# Vocodec_rev2_2.net
KiCad netlist of a schematic drawn in EAGLE
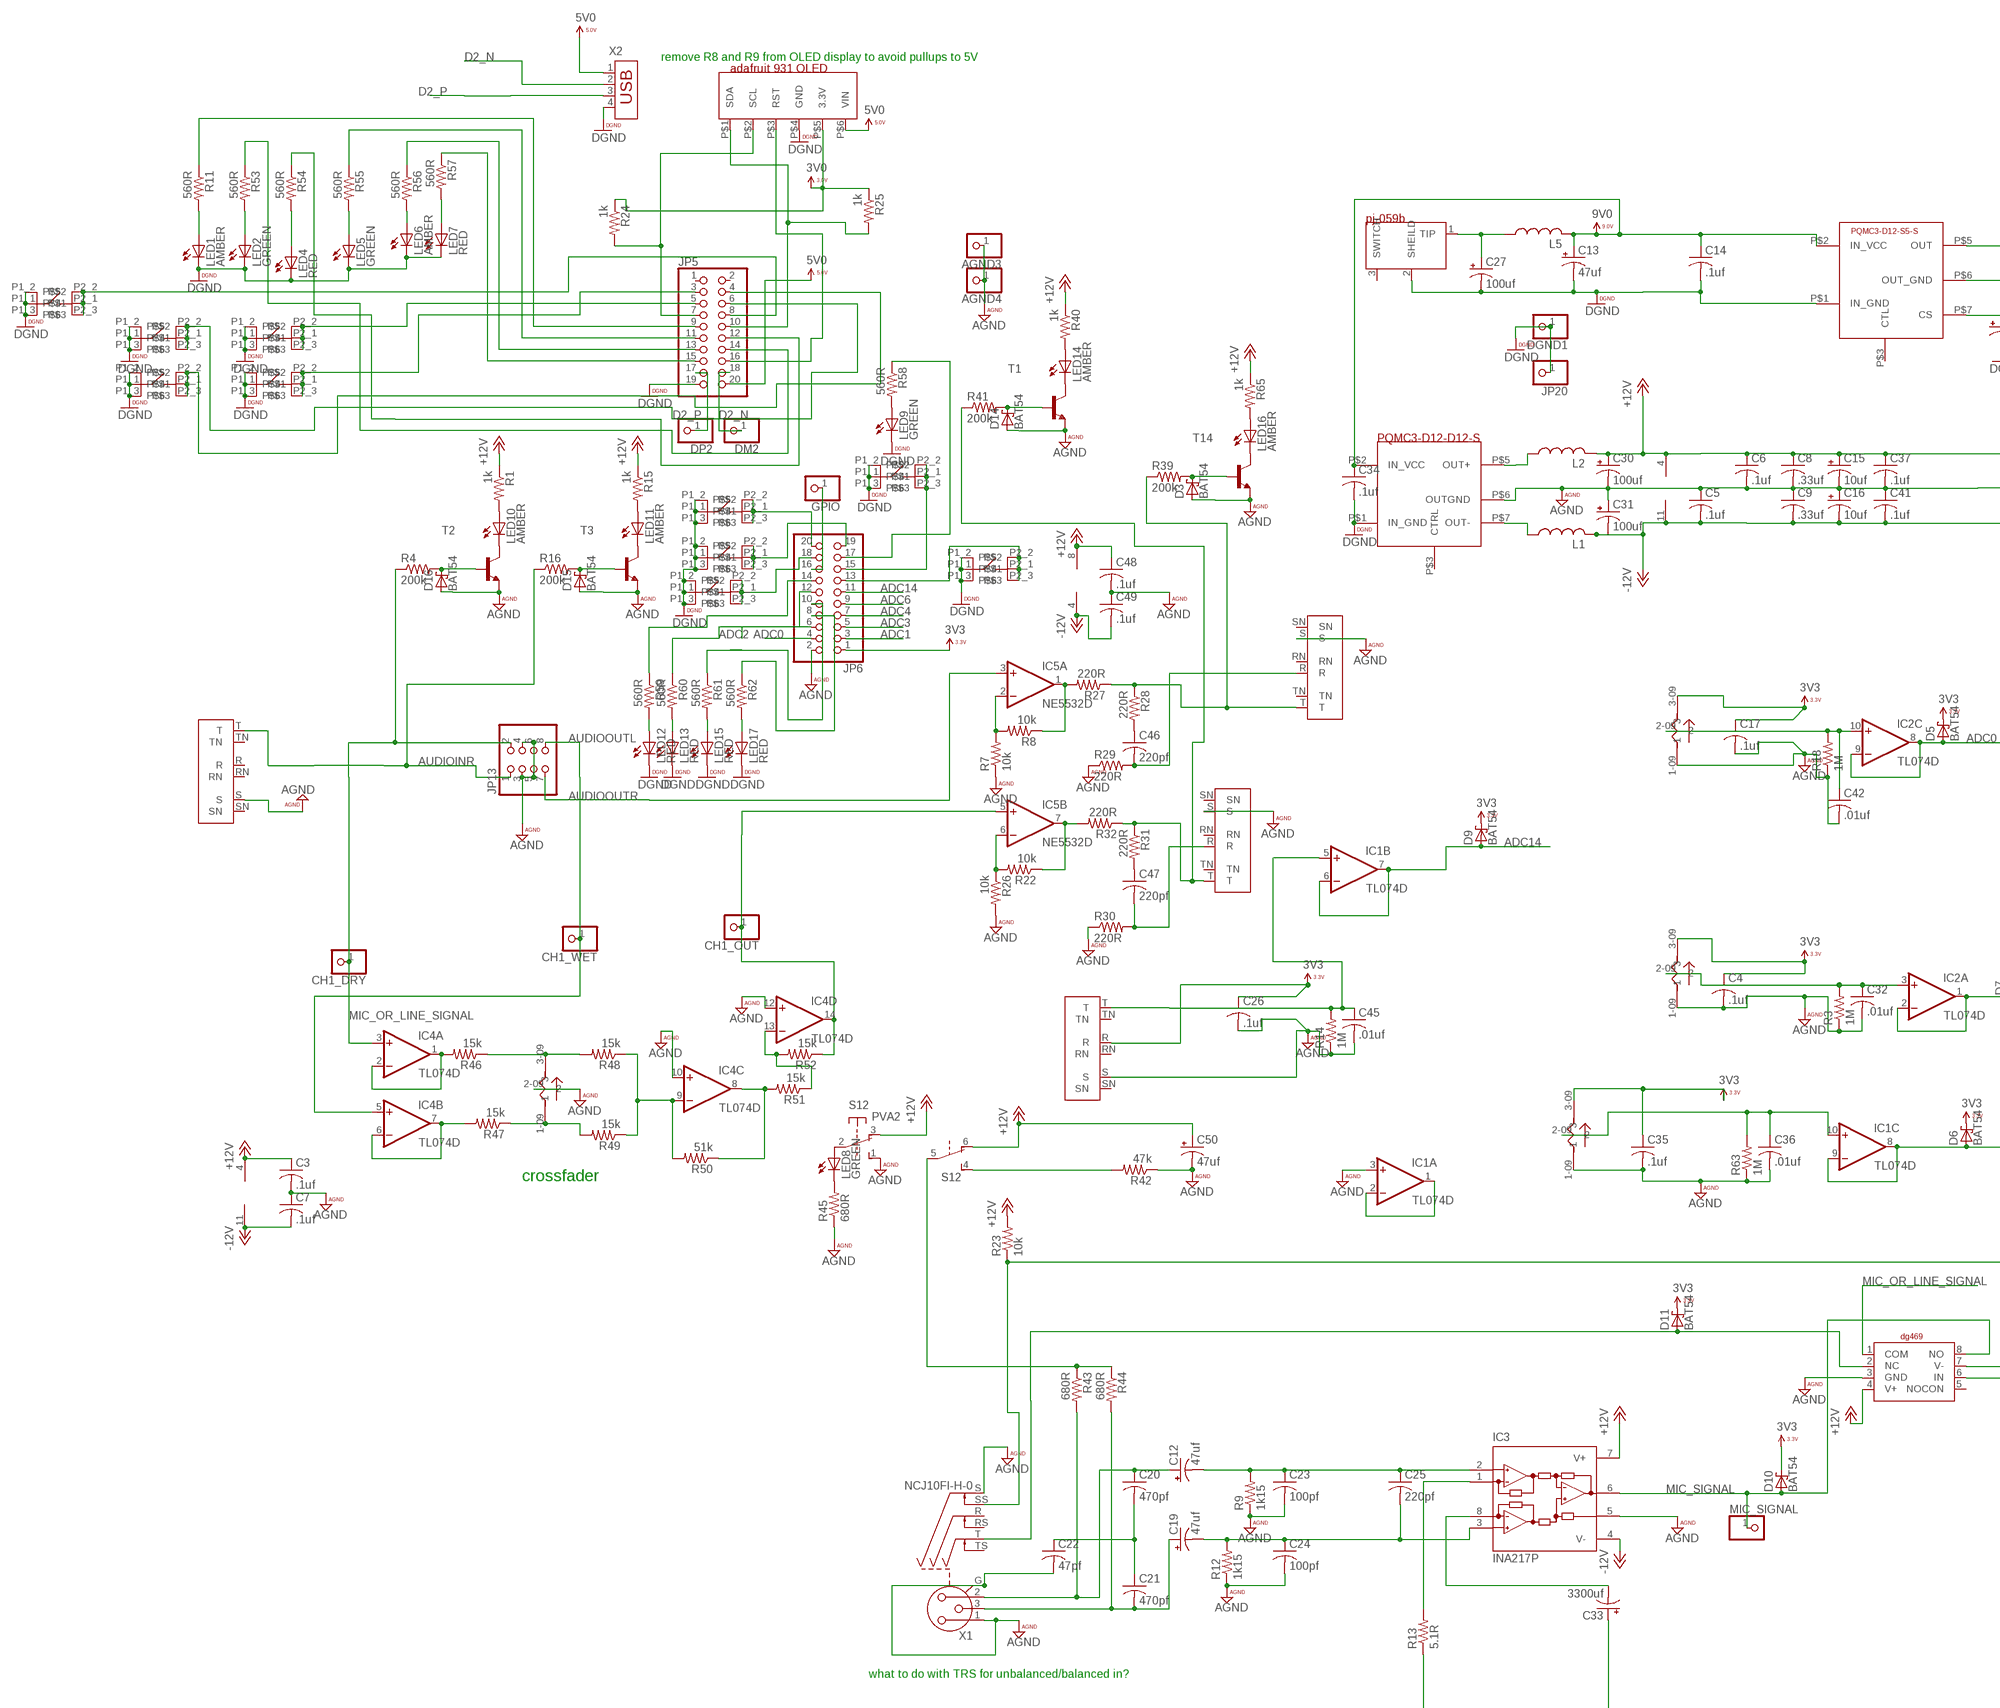
[diagram p0: schematic, sheet 1, part 1 of 3]
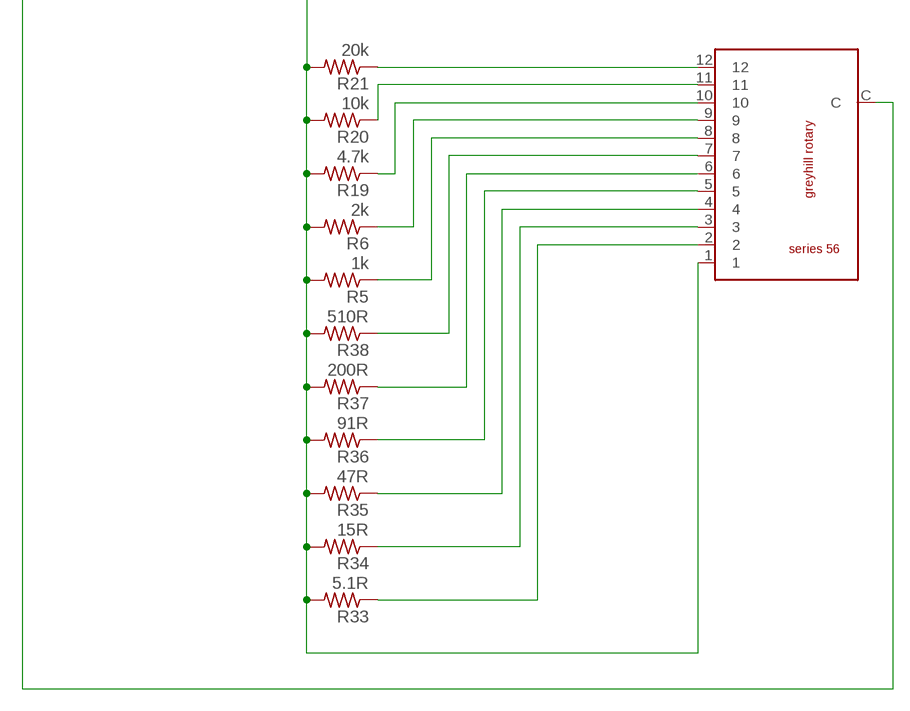
[diagram p1: schematic, sheet 1, part 2 of 3]
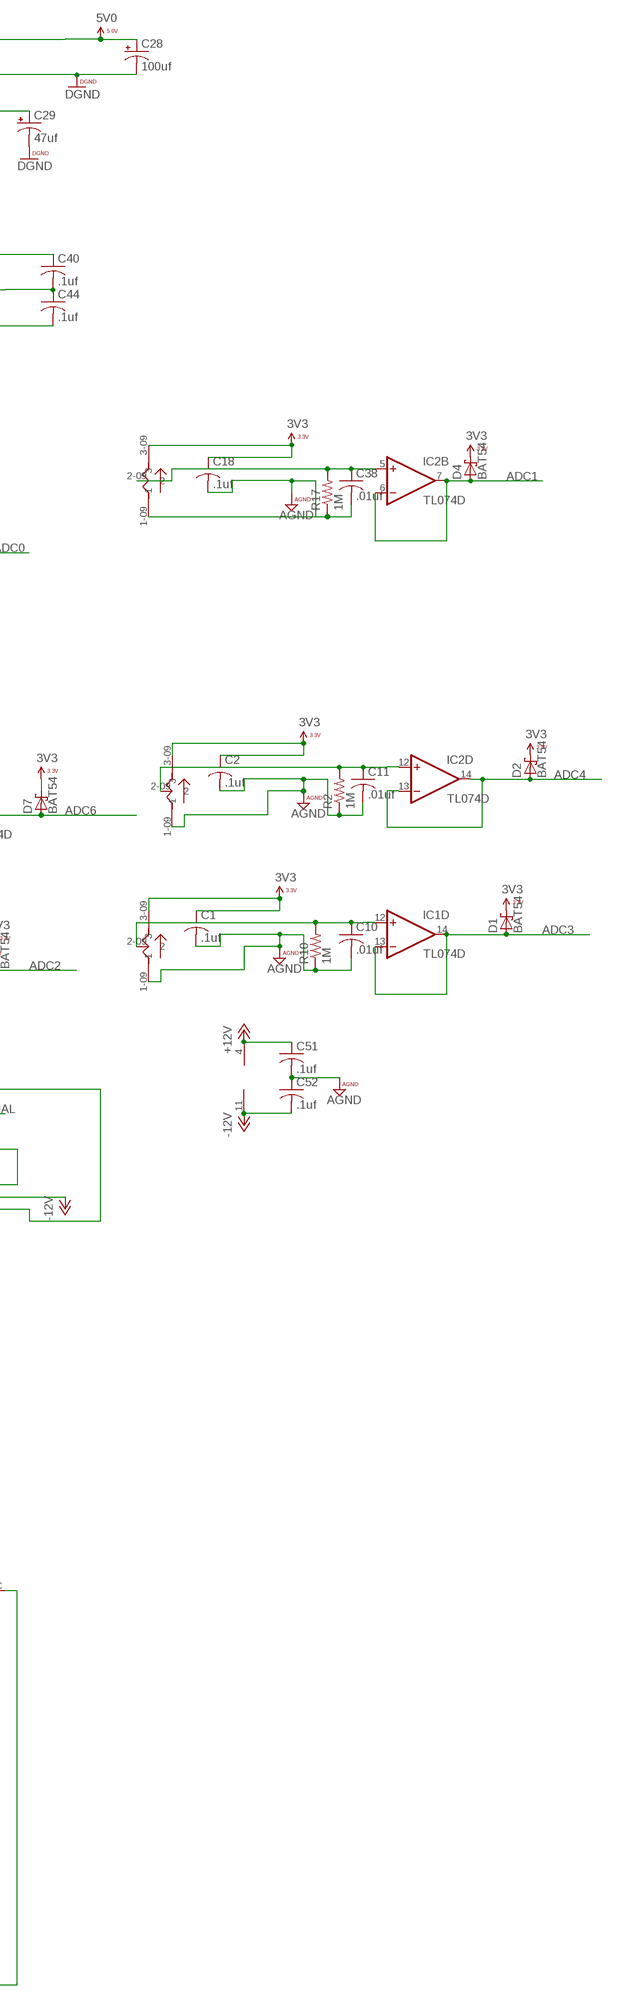
[diagram p2: schematic, sheet 1, part 3 of 3]

(export (version "E")
  (design (tool "Eeschema 10.0.6"))
  (components
    (comp (ref "AGND3")
      (value "PINHD-1X1")
      (footprint "eagle-import:1X01")
      (fields (field (name "PARTNO") "*DNP"))
      (libsource (lib "eagle-import") (part "PINHD-1X1"))
    )
    (comp (ref "AGND4")
      (value "PINHD-1X1")
      (footprint "eagle-import:1X01")
      (fields (field (name "PARTNO") "*DNP"))
      (libsource (lib "eagle-import") (part "PINHD-1X1"))
    )
    (comp (ref "C1")
      (value ".1uf")
      (footprint "eagle-import:C0603")
      (fields (field (name "PARTNO") "CC0603KRX7R8BB104"))
      (libsource (lib "eagle-import") (part "C-USC0603"))
    )
    (comp (ref "C2")
      (value ".1uf")
      (footprint "eagle-import:C0603")
      (fields (field (name "PARTNO") "CC0603KRX7R8BB104"))
      (libsource (lib "eagle-import") (part "C-USC0603"))
    )
    (comp (ref "C3")
      (value ".1uf")
      (footprint "eagle-import:C0603")
      (fields (field (name "PARTNO") "CC0603KRX7R8BB104"))
      (libsource (lib "eagle-import") (part "C-USC0603"))
    )
    (comp (ref "C4")
      (value ".1uf")
      (footprint "eagle-import:C0603")
      (fields (field (name "PARTNO") "CC0603KRX7R8BB104"))
      (libsource (lib "eagle-import") (part "C-USC0603"))
    )
    (comp (ref "C5")
      (value ".1uf")
      (footprint "eagle-import:C0603")
      (fields (field (name "PARTNO") "CC0603KRX7R8BB104"))
      (libsource (lib "eagle-import") (part "C-USC0603"))
    )
    (comp (ref "C6")
      (value ".1uf")
      (footprint "eagle-import:C0603")
      (fields (field (name "PARTNO") "CC0603KRX7R8BB104"))
      (libsource (lib "eagle-import") (part "C-USC0603"))
    )
    (comp (ref "C7")
      (value ".1uf")
      (footprint "eagle-import:C0603")
      (fields (field (name "PARTNO") "CC0603KRX7R8BB104"))
      (libsource (lib "eagle-import") (part "C-USC0603"))
    )
    (comp (ref "C8")
      (value ".33uf")
      (footprint "eagle-import:C0603")
      (fields (field (name "PARTNO") "C1608X7R1H334K080AC"))
      (libsource (lib "eagle-import") (part "C-USC0603"))
    )
    (comp (ref "C9")
      (value ".33uf")
      (footprint "eagle-import:C0603")
      (fields (field (name "PARTNO") "C1608X7R1H334K080AC"))
      (libsource (lib "eagle-import") (part "C-USC0603"))
    )
    (comp (ref "C10")
      (value ".01uf")
      (footprint "eagle-import:C0603")
      (fields (field (name "PARTNO") "CC0603KRX7R8BB103"))
      (libsource (lib "eagle-import") (part "C-USC0603"))
    )
    (comp (ref "C11")
      (value ".01uf")
      (footprint "eagle-import:C0603")
      (fields (field (name "PARTNO") "CC0603KRX7R8BB103"))
      (libsource (lib "eagle-import") (part "C-USC0603"))
    )
    (comp (ref "C12")
      (value "47uf")
      (footprint "eagle-import:PANASONIC_E")
      (fields (field (name "PARTNO") "EEE-1VA470AP"))
      (libsource (lib "eagle-import") (part "CPOL-USE"))
    )
    (comp (ref "C13")
      (value "47uf")
      (footprint "eagle-import:PANASONIC_E")
      (fields (field (name "PARTNO") "EEE-1VA470AP"))
      (libsource (lib "eagle-import") (part "CPOL-USE"))
    )
    (comp (ref "C14")
      (value ".1uf")
      (footprint "eagle-import:C0603")
      (fields (field (name "PARTNO") "CC0603KRX7R8BB104"))
      (libsource (lib "eagle-import") (part "C-USC0603"))
    )
    (comp (ref "C15")
      (value "10uf")
      (footprint "eagle-import:PANASONIC_C")
      (fields (field (name "PARTNO") "EEE-1VA100AR"))
      (libsource (lib "eagle-import") (part "CPOL-USC"))
    )
    (comp (ref "C16")
      (value "10uf")
      (footprint "eagle-import:PANASONIC_C")
      (fields (field (name "PARTNO") "EEE-1VA100AR"))
      (libsource (lib "eagle-import") (part "CPOL-USC"))
    )
    (comp (ref "C17")
      (value ".1uf")
      (footprint "eagle-import:C0603")
      (fields (field (name "PARTNO") "CC0603KRX7R8BB104"))
      (libsource (lib "eagle-import") (part "C-USC0603"))
    )
    (comp (ref "C18")
      (value ".1uf")
      (footprint "eagle-import:C0603")
      (fields (field (name "PARTNO") "CC0603KRX7R8BB104"))
      (libsource (lib "eagle-import") (part "C-USC0603"))
    )
    (comp (ref "C19")
      (value "47uf")
      (footprint "eagle-import:PANASONIC_E")
      (fields (field (name "PARTNO") "EEE-1VA470AP"))
      (libsource (lib "eagle-import") (part "CPOL-USE"))
    )
    (comp (ref "C20")
      (value "470pf")
      (footprint "eagle-import:C0603")
      (fields (field (name "PARTNO") "CC0603JRNPO9BN471"))
      (libsource (lib "eagle-import") (part "C-USC0603"))
    )
    (comp (ref "C21")
      (value "470pf")
      (footprint "eagle-import:C0603")
      (fields (field (name "PARTNO") "CC0603JRNPO9BN471"))
      (libsource (lib "eagle-import") (part "C-USC0603"))
    )
    (comp (ref "C22")
      (value "47pf")
      (footprint "eagle-import:C0603")
      (fields (field (name "PARTNO") "C0603C470J5GACTU"))
      (libsource (lib "eagle-import") (part "C-USC0603"))
    )
    (comp (ref "C23")
      (value "100pf")
      (footprint "eagle-import:C0603")
      (fields (field (name "PARTNO") "C0603C101J3GACTU"))
      (libsource (lib "eagle-import") (part "C-USC0603"))
    )
    (comp (ref "C24")
      (value "100pf")
      (footprint "eagle-import:C0603")
      (fields (field (name "PARTNO") "C0603C101J3GACTU"))
      (libsource (lib "eagle-import") (part "C-USC0603"))
    )
    (comp (ref "C25")
      (value "220pf")
      (footprint "eagle-import:C0603")
      (fields (field (name "PARTNO") "CC0603JRNPO9BN221"))
      (libsource (lib "eagle-import") (part "C-USC0603"))
    )
    (comp (ref "C26")
      (value ".1uf")
      (footprint "eagle-import:C0603")
      (fields (field (name "PARTNO") "CC0603KRX7R8BB104"))
      (libsource (lib "eagle-import") (part "C-USC0603"))
    )
    (comp (ref "C27")
      (value "100uf")
      (footprint "eagle-import:PANASONIC_F")
      (fields (field (name "PARTNO") "EEE-1EA101P"))
      (libsource (lib "eagle-import") (part "CPOL-USF"))
    )
    (comp (ref "C28")
      (value "100uf")
      (footprint "eagle-import:PANASONIC_F")
      (fields (field (name "PARTNO") "EEE-1EA101P"))
      (libsource (lib "eagle-import") (part "CPOL-USF"))
    )
    (comp (ref "C29")
      (value "47uf")
      (footprint "eagle-import:PANASONIC_E")
      (fields (field (name "PARTNO") "EEE-1VA470AP"))
      (libsource (lib "eagle-import") (part "CPOL-USE"))
    )
    (comp (ref "C30")
      (value "100uf")
      (footprint "eagle-import:PANASONIC_F")
      (fields (field (name "PARTNO") "EEE-1EA101P"))
      (libsource (lib "eagle-import") (part "CPOL-USF"))
    )
    (comp (ref "C31")
      (value "100uf")
      (footprint "eagle-import:PANASONIC_F")
      (fields (field (name "PARTNO") "EEE-1EA101P"))
      (libsource (lib "eagle-import") (part "CPOL-USF"))
    )
    (comp (ref "C32")
      (value ".01uf")
      (footprint "eagle-import:C0603")
      (fields (field (name "PARTNO") "CC0603KRX7R8BB103"))
      (libsource (lib "eagle-import") (part "C-USC0603"))
    )
    (comp (ref "C33")
      (value "3300uf")
      (footprint "eagle-import:E5-13")
      (fields (field (name "PARTNO") "EEU-FR1A332"))
      (libsource (lib "eagle-import") (part "CPOL-USE5-13"))
    )
    (comp (ref "C34")
      (value ".1uf")
      (footprint "eagle-import:C0603")
      (fields (field (name "PARTNO") "CC0603KRX7R8BB104"))
      (libsource (lib "eagle-import") (part "C-USC0603"))
    )
    (comp (ref "C35")
      (value ".1uf")
      (footprint "eagle-import:C0603")
      (fields (field (name "PARTNO") "CC0603KRX7R8BB104"))
      (libsource (lib "eagle-import") (part "C-USC0603"))
    )
    (comp (ref "C36")
      (value ".01uf")
      (footprint "eagle-import:C0603")
      (fields (field (name "PARTNO") "CC0603KRX7R8BB103"))
      (libsource (lib "eagle-import") (part "C-USC0603"))
    )
    (comp (ref "C37")
      (value ".1uf")
      (footprint "eagle-import:C0603")
      (fields (field (name "PARTNO") "CC0603KRX7R8BB104"))
      (libsource (lib "eagle-import") (part "C-USC0603"))
    )
    (comp (ref "C38")
      (value ".01uf")
      (footprint "eagle-import:C0603")
      (fields (field (name "PARTNO") "CC0603KRX7R8BB103"))
      (libsource (lib "eagle-import") (part "C-USC0603"))
    )
    (comp (ref "C40")
      (value ".1uf")
      (footprint "eagle-import:C0603")
      (fields (field (name "PARTNO") "CC0603KRX7R8BB104"))
      (libsource (lib "eagle-import") (part "C-USC0603"))
    )
    (comp (ref "C41")
      (value ".1uf")
      (footprint "eagle-import:C0603")
      (fields (field (name "PARTNO") "CC0603KRX7R8BB104"))
      (libsource (lib "eagle-import") (part "C-USC0603"))
    )
    (comp (ref "C42")
      (value ".01uf")
      (footprint "eagle-import:C0603")
      (fields (field (name "PARTNO") "CC0603KRX7R8BB103"))
      (libsource (lib "eagle-import") (part "C-USC0603"))
    )
    (comp (ref "C44")
      (value ".1uf")
      (footprint "eagle-import:C0603")
      (fields (field (name "PARTNO") "CC0603KRX7R8BB104"))
      (libsource (lib "eagle-import") (part "C-USC0603"))
    )
    (comp (ref "C45")
      (value ".01uf")
      (footprint "eagle-import:C0603")
      (fields (field (name "PARTNO") "CC0603KRX7R8BB103"))
      (libsource (lib "eagle-import") (part "C-USC0603"))
    )
    (comp (ref "C46")
      (value "220pf")
      (footprint "eagle-import:C0603")
      (fields (field (name "PARTNO") "CC0603JRNPO9BN221"))
      (libsource (lib "eagle-import") (part "C-USC0603"))
    )
    (comp (ref "C47")
      (value "220pf")
      (footprint "eagle-import:C0603")
      (fields (field (name "PARTNO") "CC0603JRNPO9BN221"))
      (libsource (lib "eagle-import") (part "C-USC0603"))
    )
    (comp (ref "C48")
      (value ".1uf")
      (footprint "eagle-import:C0603")
      (fields (field (name "PARTNO") "CC0603KRX7R8BB104"))
      (libsource (lib "eagle-import") (part "C-USC0603"))
    )
    (comp (ref "C49")
      (value ".1uf")
      (footprint "eagle-import:C0603")
      (fields (field (name "PARTNO") "CC0603KRX7R8BB104"))
      (libsource (lib "eagle-import") (part "C-USC0603"))
    )
    (comp (ref "C50")
      (value "47uf")
      (footprint "eagle-import:PANASONIC_E")
      (fields (field (name "PARTNO") "EEE-1VA470AP"))
      (libsource (lib "eagle-import") (part "CPOL-USE"))
    )
    (comp (ref "C51")
      (value ".1uf")
      (footprint "eagle-import:C0603")
      (fields (field (name "PARTNO") "CC0603KRX7R8BB104"))
      (libsource (lib "eagle-import") (part "C-USC0603"))
    )
    (comp (ref "C52")
      (value ".1uf")
      (footprint "eagle-import:C0603")
      (fields (field (name "PARTNO") "CC0603KRX7R8BB104"))
      (libsource (lib "eagle-import") (part "C-USC0603"))
    )
    (comp (ref "CH1_DRY")
      (value "PINHD-1X1")
      (footprint "eagle-import:1X01")
      (fields (field (name "PARTNO") "*DNP"))
      (libsource (lib "eagle-import") (part "PINHD-1X1"))
    )
    (comp (ref "CH1_OUT")
      (value "PINHD-1X1")
      (footprint "eagle-import:1X01")
      (fields (field (name "PARTNO") "*DNP"))
      (libsource (lib "eagle-import") (part "PINHD-1X1"))
    )
    (comp (ref "CH1_WET")
      (value "PINHD-1X1")
      (footprint "eagle-import:1X01")
      (fields (field (name "PARTNO") "*DNP"))
      (libsource (lib "eagle-import") (part "PINHD-1X1"))
    )
    (comp (ref "D1")
      (value "BAT54")
      (footprint "eagle-import:SOT23")
      (libsource (lib "eagle-import") (part "BAT54"))
    )
    (comp (ref "D2")
      (value "BAT54")
      (footprint "eagle-import:SOT23")
      (libsource (lib "eagle-import") (part "BAT54"))
    )
    (comp (ref "D3")
      (value "BAT54")
      (footprint "eagle-import:SOT23")
      (libsource (lib "eagle-import") (part "BAT54"))
    )
    (comp (ref "D4")
      (value "BAT54")
      (footprint "eagle-import:SOT23")
      (libsource (lib "eagle-import") (part "BAT54"))
    )
    (comp (ref "D5")
      (value "BAT54")
      (footprint "eagle-import:SOT23")
      (libsource (lib "eagle-import") (part "BAT54"))
    )
    (comp (ref "D6")
      (value "BAT54")
      (footprint "eagle-import:SOT23")
      (libsource (lib "eagle-import") (part "BAT54"))
    )
    (comp (ref "D7")
      (value "BAT54")
      (footprint "eagle-import:SOT23")
      (libsource (lib "eagle-import") (part "BAT54"))
    )
    (comp (ref "D9")
      (value "BAT54")
      (footprint "eagle-import:SOT23")
      (libsource (lib "eagle-import") (part "BAT54"))
    )
    (comp (ref "D10")
      (value "BAT54")
      (footprint "eagle-import:SOT23")
      (libsource (lib "eagle-import") (part "BAT54"))
    )
    (comp (ref "D11")
      (value "BAT54")
      (footprint "eagle-import:SOT23")
      (libsource (lib "eagle-import") (part "BAT54"))
    )
    (comp (ref "D14")
      (value "BAT54")
      (footprint "eagle-import:SOT23")
      (libsource (lib "eagle-import") (part "BAT54"))
    )
    (comp (ref "D15")
      (value "BAT54")
      (footprint "eagle-import:SOT23")
      (libsource (lib "eagle-import") (part "BAT54"))
    )
    (comp (ref "D16")
      (value "BAT54")
      (footprint "eagle-import:SOT23")
      (libsource (lib "eagle-import") (part "BAT54"))
    )
    (comp (ref "DGND1")
      (value "PINHD-1X1")
      (footprint "eagle-import:1X01")
      (fields (field (name "PARTNO") "*DNP"))
      (libsource (lib "eagle-import") (part "PINHD-1X1"))
    )
    (comp (ref "DM2")
      (value "PINHD-1X1")
      (footprint "eagle-import:1X01")
      (fields (field (name "PARTNO") "*DNP"))
      (libsource (lib "eagle-import") (part "PINHD-1X1"))
    )
    (comp (ref "DP2")
      (value "PINHD-1X1")
      (footprint "eagle-import:1X01")
      (fields (field (name "PARTNO") "*DNP"))
      (libsource (lib "eagle-import") (part "PINHD-1X1"))
    )
    (comp (ref "GPIO")
      (value "PINHD-1X1")
      (footprint "eagle-import:1X01")
      (fields (field (name "PARTNO") "*DNP"))
      (libsource (lib "eagle-import") (part "PINHD-1X1"))
    )
    (comp (ref "IC1")
      (value "TL074D")
      (footprint "eagle-import:SO14")
      (fields (field (name "PARTNO") "TL074CDR"))
      (libsource (lib "eagle-import") (part "TL074D"))
    )
    (comp (ref "IC2")
      (value "TL074D")
      (footprint "eagle-import:SO14")
      (fields (field (name "PARTNO") "TL074CDR"))
      (libsource (lib "eagle-import") (part "TL074D"))
    )
    (comp (ref "IC3")
      (value "INA217P")
      (footprint "eagle-import:DIL08")
      (fields
        (field (name "MF") "TEXAS INSTRUMENTS")
        (field (name "MPN") "INA217AIP")
        (field (name "PARTNO") "*DNP")
      )
      (libsource (lib "eagle-import") (part "INA217P"))
    )
    (comp (ref "IC4")
      (value "TL074D")
      (footprint "eagle-import:SO14")
      (fields (field (name "PARTNO") "TL074CDR"))
      (libsource (lib "eagle-import") (part "TL074D"))
    )
    (comp (ref "IC5")
      (value "NE5532D")
      (footprint "eagle-import:SO08")
      (fields (field (name "PARTNO") "NE5532DR"))
      (libsource (lib "eagle-import") (part "NE5532D"))
    )
    (comp (ref "IC11")
      (value "PQMC3-D12-D12-S")
      (footprint "eagle-import:PQMC3-D12-D12-S")
      (libsource (lib "eagle-import") (part "PQMC3-D12-D12-S"))
    )
    (comp (ref "IC12")
      (value "PQMC3-D12-S5-S")
      (footprint "eagle-import:PQMC3-D12-D12-S")
      (libsource (lib "eagle-import") (part "PQMC3-D12-S5-S"))
    )
    (comp (ref "IC13")
      (value "DG469")
      (footprint "eagle-import:SO8")
      (fields (field (name "PARTNO") "DG469EY-T1-E3"))
      (libsource (lib "eagle-import") (part "DG469"))
    )
    (comp (ref "J1")
      (value "NRJ6HF2")
      (footprint "eagle-import:NRJ6HF2")
      (fields (field (name "PARTNO") "NRJ6HF"))
      (libsource (lib "eagle-import") (part "NRJ6HF2"))
    )
    (comp (ref "J3")
      (value "NRJ6HF2")
      (footprint "eagle-import:NRJ6HF2")
      (fields (field (name "PARTNO") "NRJ6HF"))
      (libsource (lib "eagle-import") (part "NRJ6HF2"))
    )
    (comp (ref "J4")
      (value "NRJ6HF2")
      (footprint "eagle-import:NRJ6HF2")
      (fields (field (name "PARTNO") "NRJ6HF"))
      (libsource (lib "eagle-import") (part "NRJ6HF2"))
    )
    (comp (ref "J9")
      (value "NRJ6HF2")
      (footprint "eagle-import:NRJ6HF2")
      (fields (field (name "PARTNO") "NRJ6HF"))
      (libsource (lib "eagle-import") (part "NRJ6HF2"))
    )
    (comp (ref "J10")
      (value "PJ-059B")
      (footprint "eagle-import:PJ-059B")
      (fields (field (name "PARTNO") "PJ-059A"))
      (libsource (lib "eagle-import") (part "PJ-059B"))
    )
    (comp (ref "JP5")
      (value "PINHD-2X10")
      (footprint "eagle-import:2X10")
      (fields (field (name "PARTNO") "PRPC010DAAN-RC"))
      (libsource (lib "eagle-import") (part "PINHD-2X10"))
    )
    (comp (ref "JP6")
      (value "PINHD-2X10")
      (footprint "eagle-import:2X10")
      (fields (field (name "PARTNO") "PRPC010DAAN-RC"))
      (libsource (lib "eagle-import") (part "PINHD-2X10"))
    )
    (comp (ref "JP13")
      (value "PINHD-2X4")
      (footprint "eagle-import:2X04")
      (fields (field (name "PARTNO") "PRPC004DAAN-RC"))
      (libsource (lib "eagle-import") (part "PINHD-2X4"))
    )
    (comp (ref "JP20")
      (value "PINHD-1X1")
      (footprint "eagle-import:1X01")
      (fields (field (name "PARTNO") "*DNP"))
      (libsource (lib "eagle-import") (part "PINHD-1X1"))
    )
    (comp (ref "L1")
      (value "L-US6000-XXX-RC")
      (footprint "eagle-import:6000-XXXX-RC")
      (fields (field (name "PARTNO") "RLB9012-100KL"))
      (libsource (lib "eagle-import") (part "L-US6000-XXX-RC"))
    )
    (comp (ref "L2")
      (value "L-US6000-XXX-RC")
      (footprint "eagle-import:6000-XXXX-RC")
      (fields (field (name "PARTNO") "RLB9012-100KL"))
      (libsource (lib "eagle-import") (part "L-US6000-XXX-RC"))
    )
    (comp (ref "L5")
      (value "L-US6000-XXX-RC")
      (footprint "eagle-import:6000-XXXX-RC")
      (fields (field (name "PARTNO") "RLB9012-100KL"))
      (libsource (lib "eagle-import") (part "L-US6000-XXX-RC"))
    )
    (comp (ref "LED1")
      (value "AMBER")
      (footprint "eagle-import:PLCC2")
      (fields (field (name "PARTNO") "HSMU-A100-S00J1"))
      (libsource (lib "eagle-import") (part "_T679-?-1E1F1LG"))
    )
    (comp (ref "LED2")
      (value "GREEN")
      (footprint "eagle-import:PLCC2")
      (fields (field (name "PARTNO") "HSMM-A101-R00J1"))
      (libsource (lib "eagle-import") (part "_T679-?-1E1F1LG"))
    )
    (comp (ref "LED4")
      (value "RED")
      (footprint "eagle-import:PLCC2")
      (fields (field (name "PARTNO") "HSMZ-A100-R00J1"))
      (libsource (lib "eagle-import") (part "_T679-?-1E1F1LG"))
    )
    (comp (ref "LED5")
      (value "GREEN")
      (footprint "eagle-import:PLCC2")
      (fields (field (name "PARTNO") "HSMM-A101-R00J1"))
      (libsource (lib "eagle-import") (part "_T679-?-1E1F1LG"))
    )
    (comp (ref "LED6")
      (value "AMBER")
      (footprint "eagle-import:PLCC2")
      (fields (field (name "PARTNO") "HSMU-A100-S00J1"))
      (libsource (lib "eagle-import") (part "_T679-?-1E1F1LG"))
    )
    (comp (ref "LED7")
      (value "RED")
      (footprint "eagle-import:PLCC2")
      (fields (field (name "PARTNO") "HSMZ-A100-R00J1"))
      (libsource (lib "eagle-import") (part "_T679-?-1E1F1LG"))
    )
    (comp (ref "LED8")
      (value "GREEN")
      (footprint "eagle-import:PLCC2")
      (fields (field (name "PARTNO") "HSMM-A101-R00J1"))
      (libsource (lib "eagle-import") (part "_T679-?-1E1F1LG"))
    )
    (comp (ref "LED9")
      (value "GREEN")
      (footprint "eagle-import:PLCC2")
      (fields (field (name "PARTNO") "HSMM-A101-R00J1"))
      (libsource (lib "eagle-import") (part "_T679-?-1E1F1LG"))
    )
    (comp (ref "LED10")
      (value "AMBER")
      (footprint "eagle-import:PLCC2")
      (fields (field (name "PARTNO") "HSMU-A100-S00J1"))
      (libsource (lib "eagle-import") (part "_T679-?-1E1F1LG"))
    )
    (comp (ref "LED11")
      (value "AMBER")
      (footprint "eagle-import:PLCC2")
      (fields (field (name "PARTNO") "HSMU-A100-S00J1"))
      (libsource (lib "eagle-import") (part "_T679-?-1E1F1LG"))
    )
    (comp (ref "LED12")
      (value "RED")
      (footprint "eagle-import:PLCC2")
      (fields (field (name "PARTNO") "HSMZ-A100-R00J1"))
      (libsource (lib "eagle-import") (part "_T679-?-1E1F1LG"))
    )
    (comp (ref "LED13")
      (value "RED")
      (footprint "eagle-import:PLCC2")
      (fields (field (name "PARTNO") "HSMZ-A100-R00J1"))
      (libsource (lib "eagle-import") (part "_T679-?-1E1F1LG"))
    )
    (comp (ref "LED14")
      (value "AMBER")
      (footprint "eagle-import:PLCC2")
      (fields (field (name "PARTNO") "HSMU-A100-S00J1"))
      (libsource (lib "eagle-import") (part "_T679-?-1E1F1LG"))
    )
    (comp (ref "LED15")
      (value "RED")
      (footprint "eagle-import:PLCC2")
      (fields (field (name "PARTNO") "HSMZ-A100-R00J1"))
      (libsource (lib "eagle-import") (part "_T679-?-1E1F1LG"))
    )
    (comp (ref "LED16")
      (value "AMBER")
      (footprint "eagle-import:PLCC2")
      (fields (field (name "PARTNO") "HSMU-A100-S00J1"))
      (libsource (lib "eagle-import") (part "_T679-?-1E1F1LG"))
    )
    (comp (ref "LED17")
      (value "RED")
      (footprint "eagle-import:PLCC2")
      (fields (field (name "PARTNO") "HSMZ-A100-R00J1"))
      (libsource (lib "eagle-import") (part "_T679-?-1E1F1LG"))
    )
    (comp (ref "MIC_SIGNAL")
      (value "PINHD-1X1")
      (footprint "eagle-import:1X01")
      (fields (field (name "PARTNO") "*DNP"))
      (libsource (lib "eagle-import") (part "PINHD-1X1"))
    )
    (comp (ref "OLED1")
      (value "ADAFRUIT_931_OLED_128X32")
      (footprint "eagle-import:ADAFRUIT_128X32_OLED")
      (fields (field (name "PARTNO") "*DNP"))
      (libsource (lib "eagle-import") (part "ADAFRUIT_931_OLED_128X32"))
    )
    (comp (ref "R1")
      (value "1k")
      (footprint "eagle-import:R0603")
      (fields (field (name "PARTNO") "ESR03EZPF1001"))
      (libsource (lib "eagle-import") (part "R-US_R0603"))
    )
    (comp (ref "R2")
      (value "1M")
      (footprint "eagle-import:R0603")
      (fields (field (name "PARTNO") "CRCW06031M00FKEAHP"))
      (libsource (lib "eagle-import") (part "R-US_R0603"))
    )
    (comp (ref "R3")
      (value "1M")
      (footprint "eagle-import:R0603")
      (fields (field (name "PARTNO") "CRCW06031M00FKEAHP"))
      (libsource (lib "eagle-import") (part "R-US_R0603"))
    )
    (comp (ref "R4")
      (value "200k")
      (footprint "eagle-import:R0603")
      (fields (field (name "PARTNO") "ESR03EZPJ204"))
      (libsource (lib "eagle-import") (part "R-US_R0603"))
    )
    (comp (ref "R5")
      (value "1k")
      (footprint "eagle-import:R0603")
      (fields (field (name "PARTNO") "ESR03EZPF1001"))
      (libsource (lib "eagle-import") (part "R-US_R0603"))
    )
    (comp (ref "R6")
      (value "2k")
      (footprint "eagle-import:R0603")
      (fields (field (name "PARTNO") "ERJ-PA3F2001V"))
      (libsource (lib "eagle-import") (part "R-US_R0603"))
    )
    (comp (ref "R7")
      (value "10k")
      (footprint "eagle-import:R0603")
      (fields (field (name "PARTNO") "ESR03EZPF1002"))
      (libsource (lib "eagle-import") (part "R-US_R0603"))
    )
    (comp (ref "R8")
      (value "10k")
      (footprint "eagle-import:R0603")
      (fields (field (name "PARTNO") "ESR03EZPF1002"))
      (libsource (lib "eagle-import") (part "R-US_R0603"))
    )
    (comp (ref "R9")
      (value "1k15")
      (footprint "eagle-import:R0603")
      (fields (field (name "PARTNO") "ERA-3AEB1151V"))
      (libsource (lib "eagle-import") (part "R-US_R0603"))
    )
    (comp (ref "R10")
      (value "1M")
      (footprint "eagle-import:R0603")
      (fields (field (name "PARTNO") "CRCW06031M00FKEAHP"))
      (libsource (lib "eagle-import") (part "R-US_R0603"))
    )
    (comp (ref "R11")
      (value "560R")
      (footprint "eagle-import:R0603")
      (fields (field (name "PARTNO") "ESR03EZPF5600"))
      (libsource (lib "eagle-import") (part "R-US_R0603"))
    )
    (comp (ref "R12")
      (value "1k15")
      (footprint "eagle-import:R0603")
      (fields (field (name "PARTNO") "ERA-3AEB1151V"))
      (libsource (lib "eagle-import") (part "R-US_R0603"))
    )
    (comp (ref "R13")
      (value "5.1R")
      (footprint "eagle-import:R0603")
      (fields (field (name "PARTNO") "RC0603JR-075R1L"))
      (libsource (lib "eagle-import") (part "R-US_R0603"))
    )
    (comp (ref "R14")
      (value "1M")
      (footprint "eagle-import:R0603")
      (fields (field (name "PARTNO") "CRCW06031M00FKEAHP"))
      (libsource (lib "eagle-import") (part "R-US_R0603"))
    )
    (comp (ref "R15")
      (value "1k")
      (footprint "eagle-import:R0603")
      (fields (field (name "PARTNO") "ESR03EZPF1001"))
      (libsource (lib "eagle-import") (part "R-US_R0603"))
    )
    (comp (ref "R16")
      (value "200k")
      (footprint "eagle-import:R0603")
      (fields (field (name "PARTNO") "ESR03EZPJ204"))
      (libsource (lib "eagle-import") (part "R-US_R0603"))
    )
    (comp (ref "R17")
      (value "1M")
      (footprint "eagle-import:R0603")
      (fields (field (name "PARTNO") "CRCW06031M00FKEAHP"))
      (libsource (lib "eagle-import") (part "R-US_R0603"))
    )
    (comp (ref "R18")
      (value "1M")
      (footprint "eagle-import:R0603")
      (fields (field (name "PARTNO") "CRCW06031M00FKEAHP"))
      (libsource (lib "eagle-import") (part "R-US_R0603"))
    )
    (comp (ref "R19")
      (value "4.7k")
      (footprint "eagle-import:R0603")
      (fields (field (name "PARTNO") "CRCW06034K70FKEAHP"))
      (libsource (lib "eagle-import") (part "R-US_R0603"))
    )
    (comp (ref "R20")
      (value "10k")
      (footprint "eagle-import:R0603")
      (fields (field (name "PARTNO") "ESR03EZPF1002"))
      (libsource (lib "eagle-import") (part "R-US_R0603"))
    )
    (comp (ref "R21")
      (value "20k")
      (footprint "eagle-import:R0603")
      (fields (field (name "PARTNO") "ESR03EZPF2002"))
      (libsource (lib "eagle-import") (part "R-US_R0603"))
    )
    (comp (ref "R22")
      (value "10k")
      (footprint "eagle-import:R0603")
      (fields (field (name "PARTNO") "ESR03EZPF1002"))
      (libsource (lib "eagle-import") (part "R-US_R0603"))
    )
    (comp (ref "R23")
      (value "10k")
      (footprint "eagle-import:R0603")
      (fields (field (name "PARTNO") "ESR03EZPF1002"))
      (libsource (lib "eagle-import") (part "R-US_R0603"))
    )
    (comp (ref "R24")
      (value "1k")
      (footprint "eagle-import:R0603")
      (fields (field (name "PARTNO") "ESR03EZPF1001"))
      (libsource (lib "eagle-import") (part "R-US_R0603"))
    )
    (comp (ref "R25")
      (value "1k")
      (footprint "eagle-import:R0603")
      (fields (field (name "PARTNO") "ESR03EZPF1001"))
      (libsource (lib "eagle-import") (part "R-US_R0603"))
    )
    (comp (ref "R26")
      (value "10k")
      (footprint "eagle-import:R0603")
      (fields (field (name "PARTNO") "ESR03EZPF1002"))
      (libsource (lib "eagle-import") (part "R-US_R0603"))
    )
    (comp (ref "R27")
      (value "220R")
      (footprint "eagle-import:R0603")
      (fields (field (name "PARTNO") "ESR03EZPJ221"))
      (libsource (lib "eagle-import") (part "R-US_R0603"))
    )
    (comp (ref "R28")
      (value "220R")
      (footprint "eagle-import:R0603")
      (fields (field (name "PARTNO") "ESR03EZPJ221"))
      (libsource (lib "eagle-import") (part "R-US_R0603"))
    )
    (comp (ref "R29")
      (value "220R")
      (footprint "eagle-import:R0603")
      (fields (field (name "PARTNO") "ESR03EZPJ221"))
      (libsource (lib "eagle-import") (part "R-US_R0603"))
    )
    (comp (ref "R30")
      (value "220R")
      (footprint "eagle-import:R0603")
      (fields (field (name "PARTNO") "ESR03EZPJ221"))
      (libsource (lib "eagle-import") (part "R-US_R0603"))
    )
    (comp (ref "R31")
      (value "220R")
      (footprint "eagle-import:R0603")
      (fields (field (name "PARTNO") "ESR03EZPJ221"))
      (libsource (lib "eagle-import") (part "R-US_R0603"))
    )
    (comp (ref "R32")
      (value "220R")
      (footprint "eagle-import:R0603")
      (fields (field (name "PARTNO") "ESR03EZPJ221"))
      (libsource (lib "eagle-import") (part "R-US_R0603"))
    )
    (comp (ref "R33")
      (value "5.1R")
      (footprint "eagle-import:R0603")
      (fields (field (name "PARTNO") "RC0603JR-075R1L"))
      (libsource (lib "eagle-import") (part "R-US_R0603"))
    )
    (comp (ref "R34")
      (value "15R")
      (footprint "eagle-import:R0603")
      (fields (field (name "PARTNO") "RC0603JR-0715RL"))
      (libsource (lib "eagle-import") (part "R-US_R0603"))
    )
    (comp (ref "R35")
      (value "47R")
      (footprint "eagle-import:R0603")
      (fields (field (name "PARTNO") "RC0603JR-0747RL"))
      (libsource (lib "eagle-import") (part "R-US_R0603"))
    )
    (comp (ref "R36")
      (value "91R")
      (footprint "eagle-import:R0603")
      (fields (field (name "PARTNO") "RC0603JR-0791RL"))
      (libsource (lib "eagle-import") (part "R-US_R0603"))
    )
    (comp (ref "R37")
      (value "200R")
      (footprint "eagle-import:R0603")
      (fields (field (name "PARTNO") "RC0603JR-07200RL"))
      (libsource (lib "eagle-import") (part "R-US_R0603"))
    )
    (comp (ref "R38")
      (value "510R")
      (footprint "eagle-import:R0603")
      (fields (field (name "PARTNO") "RC0603JR-07510RL"))
      (libsource (lib "eagle-import") (part "R-US_R0603"))
    )
    (comp (ref "R39")
      (value "200k")
      (footprint "eagle-import:R0603")
      (fields (field (name "PARTNO") "ESR03EZPJ204"))
      (libsource (lib "eagle-import") (part "R-US_R0603"))
    )
    (comp (ref "R40")
      (value "1k")
      (footprint "eagle-import:R0603")
      (fields (field (name "PARTNO") "ESR03EZPF1001"))
      (libsource (lib "eagle-import") (part "R-US_R0603"))
    )
    (comp (ref "R41")
      (value "200k")
      (footprint "eagle-import:R0603")
      (fields (field (name "PARTNO") "ESR03EZPJ204"))
      (libsource (lib "eagle-import") (part "R-US_R0603"))
    )
    (comp (ref "R42")
      (value "47k")
      (footprint "eagle-import:R0603")
      (fields (field (name "PARTNO") "ESR03EZPJ473"))
      (libsource (lib "eagle-import") (part "R-US_R0603"))
    )
    (comp (ref "R43")
      (value "680R")
      (footprint "eagle-import:R0603")
      (fields (field (name "PARTNO") "CRCW0603680RJNEAHP"))
      (libsource (lib "eagle-import") (part "R-US_R0603"))
    )
    (comp (ref "R44")
      (value "680R")
      (footprint "eagle-import:R0603")
      (fields (field (name "PARTNO") "CRCW0603680RJNEAHP"))
      (libsource (lib "eagle-import") (part "R-US_R0603"))
    )
    (comp (ref "R45")
      (value "680R")
      (footprint "eagle-import:R0603")
      (fields (field (name "PARTNO") "CRCW0603680RJNEAHP"))
      (libsource (lib "eagle-import") (part "R-US_R0603"))
    )
    (comp (ref "R46")
      (value "15k")
      (footprint "eagle-import:R0603")
      (fields (field (name "PARTNO") "ESR03EZPF1502"))
      (libsource (lib "eagle-import") (part "R-US_R0603"))
    )
    (comp (ref "R47")
      (value "15k")
      (footprint "eagle-import:R0603")
      (fields (field (name "PARTNO") "ESR03EZPF1502"))
      (libsource (lib "eagle-import") (part "R-US_R0603"))
    )
    (comp (ref "R48")
      (value "15k")
      (footprint "eagle-import:R0603")
      (fields (field (name "PARTNO") "ESR03EZPF1502"))
      (libsource (lib "eagle-import") (part "R-US_R0603"))
    )
    (comp (ref "R49")
      (value "15k")
      (footprint "eagle-import:R0603")
      (fields (field (name "PARTNO") "ESR03EZPF1502"))
      (libsource (lib "eagle-import") (part "R-US_R0603"))
    )
    (comp (ref "R50")
      (value "51k")
      (footprint "eagle-import:R0603")
      (fields (field (name "PARTNO") "ERJ-PA3F5102V"))
      (libsource (lib "eagle-import") (part "R-US_R0603"))
    )
    (comp (ref "R51")
      (value "15k")
      (footprint "eagle-import:R0603")
      (fields (field (name "PARTNO") "ESR03EZPF1502"))
      (libsource (lib "eagle-import") (part "R-US_R0603"))
    )
    (comp (ref "R52")
      (value "15k")
      (footprint "eagle-import:R0603")
      (fields (field (name "PARTNO") "ESR03EZPF1502"))
      (libsource (lib "eagle-import") (part "R-US_R0603"))
    )
    (comp (ref "R53")
      (value "560R")
      (footprint "eagle-import:R0603")
      (fields (field (name "PARTNO") "ESR03EZPF5600"))
      (libsource (lib "eagle-import") (part "R-US_R0603"))
    )
    (comp (ref "R54")
      (value "560R")
      (footprint "eagle-import:R0603")
      (fields (field (name "PARTNO") "ESR03EZPF5600"))
      (libsource (lib "eagle-import") (part "R-US_R0603"))
    )
    (comp (ref "R55")
      (value "560R")
      (footprint "eagle-import:R0603")
      (fields (field (name "PARTNO") "ESR03EZPF5600"))
      (libsource (lib "eagle-import") (part "R-US_R0603"))
    )
    (comp (ref "R56")
      (value "560R")
      (footprint "eagle-import:R0603")
      (fields (field (name "PARTNO") "ESR03EZPF5600"))
      (libsource (lib "eagle-import") (part "R-US_R0603"))
    )
    (comp (ref "R57")
      (value "560R")
      (footprint "eagle-import:R0603")
      (fields (field (name "PARTNO") "ESR03EZPF5600"))
      (libsource (lib "eagle-import") (part "R-US_R0603"))
    )
    (comp (ref "R58")
      (value "560R")
      (footprint "eagle-import:R0603")
      (fields (field (name "PARTNO") "ESR03EZPF5600"))
      (libsource (lib "eagle-import") (part "R-US_R0603"))
    )
    (comp (ref "R59")
      (value "560R")
      (footprint "eagle-import:R0603")
      (fields (field (name "PARTNO") "ESR03EZPF5600"))
      (libsource (lib "eagle-import") (part "R-US_R0603"))
    )
    (comp (ref "R60")
      (value "560R")
      (footprint "eagle-import:R0603")
      (fields (field (name "PARTNO") "ESR03EZPF5600"))
      (libsource (lib "eagle-import") (part "R-US_R0603"))
    )
    (comp (ref "R61")
      (value "560R")
      (footprint "eagle-import:R0603")
      (fields (field (name "PARTNO") "ESR03EZPF5600"))
      (libsource (lib "eagle-import") (part "R-US_R0603"))
    )
    (comp (ref "R62")
      (value "560R")
      (footprint "eagle-import:R0603")
      (fields (field (name "PARTNO") "ESR03EZPF5600"))
      (libsource (lib "eagle-import") (part "R-US_R0603"))
    )
    (comp (ref "R63")
      (value "1M")
      (footprint "eagle-import:R0603")
      (fields (field (name "PARTNO") "CRCW06031M00FKEAHP"))
      (libsource (lib "eagle-import") (part "R-US_R0603"))
    )
    (comp (ref "R65")
      (value "1k")
      (footprint "eagle-import:R0603")
      (fields (field (name "PARTNO") "ESR03EZPF1001"))
      (libsource (lib "eagle-import") (part "R-US_R0603"))
    )
    (comp (ref "S12")
      (value "PVA2")
      (footprint "eagle-import:PVA2F")
      (fields (field (name "PARTNO") "PVA2 OA H4 1.7N V2"))
      (libsource (lib "eagle-import") (part "PVA2"))
    )
    (comp (ref "T1")
      (value "MMBT3904LT1-NPN-SOT23-BEC")
      (footprint "eagle-import:SOT23-BEC")
      (fields (field (name "PARTNO") "MMBT3904-TP"))
      (libsource (lib "eagle-import") (part "-NPN-SOT23-BECMMBT3904LT1"))
    )
    (comp (ref "T2")
      (value "MMBT3904LT1-NPN-SOT23-BEC")
      (footprint "eagle-import:SOT23-BEC")
      (fields (field (name "PARTNO") "MMBT3904-TP"))
      (libsource (lib "eagle-import") (part "-NPN-SOT23-BECMMBT3904LT1"))
    )
    (comp (ref "T3")
      (value "MMBT3904LT1-NPN-SOT23-BEC")
      (footprint "eagle-import:SOT23-BEC")
      (fields (field (name "PARTNO") "MMBT3904-TP"))
      (libsource (lib "eagle-import") (part "-NPN-SOT23-BECMMBT3904LT1"))
    )
    (comp (ref "T14")
      (value "MMBT3904LT1-NPN-SOT23-BEC")
      (footprint "eagle-import:SOT23-BEC")
      (fields (field (name "PARTNO") "MMBT3904-TP"))
      (libsource (lib "eagle-import") (part "-NPN-SOT23-BECMMBT3904LT1"))
    )
    (comp (ref "U$1")
      (value "56DP30")
      (footprint "eagle-import:56DP30")
      (fields (field (name "PARTNO") "56DP30-01-1-AJN"))
      (libsource (lib "eagle-import") (part "56DP30"))
    )
    (comp (ref "U$7")
      (value "TL52_PLUS")
      (footprint "eagle-import:TL52_PLUS")
      (fields (field (name "PARTNO") "*DNP"))
      (libsource (lib "eagle-import") (part "TL52_PLUS"))
    )
    (comp (ref "U$11")
      (value "TL52_PLUS")
      (footprint "eagle-import:TL52_PLUS")
      (fields (field (name "PARTNO") "*DNP"))
      (libsource (lib "eagle-import") (part "TL52_PLUS"))
    )
    (comp (ref "U$12")
      (value "RK09")
      (footprint "eagle-import:RK09")
      (fields (field (name "PARTNO") "*DNP"))
      (libsource (lib "eagle-import") (part "RK09"))
    )
    (comp (ref "U$14")
      (value "RK09")
      (footprint "eagle-import:RK09")
      (fields (field (name "PARTNO") "*DNP"))
      (libsource (lib "eagle-import") (part "RK09"))
    )
    (comp (ref "U$16")
      (value "RK09")
      (footprint "eagle-import:RK09")
      (fields (field (name "PARTNO") "*DNP"))
      (libsource (lib "eagle-import") (part "RK09"))
    )
    (comp (ref "U$27")
      (value "RK09")
      (footprint "eagle-import:RK09")
      (fields (field (name "PARTNO") "*DNP"))
      (libsource (lib "eagle-import") (part "RK09"))
    )
    (comp (ref "U$28")
      (value "RK09")
      (footprint "eagle-import:RK09")
      (fields (field (name "PARTNO") "*DNP"))
      (libsource (lib "eagle-import") (part "RK09"))
    )
    (comp (ref "U$31")
      (value "RK09")
      (footprint "eagle-import:RK09")
      (fields (field (name "PARTNO") "*DNP"))
      (libsource (lib "eagle-import") (part "RK09"))
    )
    (comp (ref "U$32")
      (value "RK09")
      (footprint "eagle-import:RK09")
      (fields (field (name "PARTNO") "*DNP"))
      (libsource (lib "eagle-import") (part "RK09"))
    )
    (comp (ref "U$33")
      (value "TL52_PLUS")
      (footprint "eagle-import:TL52_PLUS")
      (fields (field (name "PARTNO") "*DNP"))
      (libsource (lib "eagle-import") (part "TL52_PLUS"))
    )
    (comp (ref "U$39")
      (value "TL52_PLUS")
      (footprint "eagle-import:TL52_PLUS")
      (fields (field (name "PARTNO") "*DNP"))
      (libsource (lib "eagle-import") (part "TL52_PLUS"))
    )
    (comp (ref "U$40")
      (value "TL52_PLUS")
      (footprint "eagle-import:TL52_PLUS")
      (fields (field (name "PARTNO") "*DNP"))
      (libsource (lib "eagle-import") (part "TL52_PLUS"))
    )
    (comp (ref "U$42")
      (value "TL52_PLUS")
      (footprint "eagle-import:TL52_PLUS")
      (fields (field (name "PARTNO") "*DNP"))
      (libsource (lib "eagle-import") (part "TL52_PLUS"))
    )
    (comp (ref "U$43")
      (value "TL52_PLUS")
      (footprint "eagle-import:TL52_PLUS")
      (fields (field (name "PARTNO") "*DNP"))
      (libsource (lib "eagle-import") (part "TL52_PLUS"))
    )
    (comp (ref "U$44")
      (value "TL52_PLUS")
      (footprint "eagle-import:TL52_PLUS")
      (fields (field (name "PARTNO") "*DNP"))
      (libsource (lib "eagle-import") (part "TL52_PLUS"))
    )
    (comp (ref "U$45")
      (value "TL52_PLUS")
      (footprint "eagle-import:TL52_PLUS")
      (fields (field (name "PARTNO") "*DNP"))
      (libsource (lib "eagle-import") (part "TL52_PLUS"))
    )
    (comp (ref "U$48")
      (value "TL52_PLUS")
      (footprint "eagle-import:TL52_PLUS")
      (fields (field (name "PARTNO") "*DNP"))
      (libsource (lib "eagle-import") (part "TL52_PLUS"))
    )
    (comp (ref "X1")
      (value "NCJ10FI-H-0")
      (footprint "eagle-import:NCJ10FI-H-0")
      (fields (field (name "PARTNO") "NCJ10FI-H-01"))
      (libsource (lib "eagle-import") (part "NCJ10FI-H-0"))
    )
    (comp (ref "X2")
      (value "USB-787616")
      (footprint "eagle-import:USB")
      (fields (field (name "PARTNO") "292303-1"))
      (libsource (lib "eagle-import") (part "USB-787616"))
    )
  )
  (nets
    (net (code "1") (name "+12V") (class "Default")
      (node (ref "C15") (pin "+") (pinfunction "+_+") (pintype "passive"))
      (node (ref "C3") (pin "1") (pinfunction "1_1") (pintype "passive"))
      (node (ref "C30") (pin "+") (pinfunction "+_+") (pintype "passive"))
      (node (ref "C37") (pin "1") (pinfunction "1_1") (pintype "passive"))
      (node (ref "C40") (pin "1") (pinfunction "1_1") (pintype "passive"))
      (node (ref "C48") (pin "1") (pinfunction "1_1") (pintype "passive"))
      (node (ref "C50") (pin "+") (pinfunction "+_+") (pintype "passive"))
      (node (ref "C51") (pin "1") (pinfunction "1_1") (pintype "passive"))
      (node (ref "C6") (pin "1") (pinfunction "1_1") (pintype "passive"))
      (node (ref "C8") (pin "1") (pinfunction "1_1") (pintype "passive"))
      (node (ref "IC1") (pin "4") (pinfunction "V+_4") (pintype "power_in"))
      (node (ref "IC13") (pin "4") (pinfunction "V+_4") (pintype "bidirectional"))
      (node (ref "IC2") (pin "4") (pinfunction "V+_4") (pintype "power_in"))
      (node (ref "IC3") (pin "7") (pinfunction "V+_7") (pintype "power_in"))
      (node (ref "IC4") (pin "4") (pinfunction "V+_4") (pintype "power_in"))
      (node (ref "IC5") (pin "8") (pinfunction "V+_8") (pintype "power_in"))
      (node (ref "L2") (pin "2") (pinfunction "2_2") (pintype "passive"))
      (node (ref "R1") (pin "1") (pinfunction "1_1") (pintype "passive"))
      (node (ref "R15") (pin "1") (pinfunction "1_1") (pintype "passive"))
      (node (ref "R23") (pin "2") (pinfunction "2_2") (pintype "passive"))
      (node (ref "R40") (pin "1") (pinfunction "1_1") (pintype "passive"))
      (node (ref "R65") (pin "1") (pinfunction "1_1") (pintype "passive"))
      (node (ref "S12") (pin "3") (pinfunction "O_3") (pintype "passive"))
      (node (ref "S12") (pin "6") (pinfunction "O_6") (pintype "passive"))
    )
    (net (code "2") (name "-12V") (class "Default")
      (node (ref "C16") (pin "-") (pinfunction "-_-") (pintype "passive"))
      (node (ref "C31") (pin "-") (pinfunction "-_-") (pintype "passive"))
      (node (ref "C41") (pin "2") (pinfunction "2_2") (pintype "passive"))
      (node (ref "C44") (pin "2") (pinfunction "2_2") (pintype "passive"))
      (node (ref "C49") (pin "2") (pinfunction "2_2") (pintype "passive"))
      (node (ref "C5") (pin "2") (pinfunction "2_2") (pintype "passive"))
      (node (ref "C52") (pin "2") (pinfunction "2_2") (pintype "passive"))
      (node (ref "C7") (pin "2") (pinfunction "2_2") (pintype "passive"))
      (node (ref "C9") (pin "2") (pinfunction "2_2") (pintype "passive"))
      (node (ref "IC1") (pin "11") (pinfunction "V-_11") (pintype "power_in"))
      (node (ref "IC13") (pin "7") (pinfunction "V-_7") (pintype "bidirectional"))
      (node (ref "IC2") (pin "11") (pinfunction "V-_11") (pintype "power_in"))
      (node (ref "IC3") (pin "4") (pinfunction "V-_4") (pintype "power_in"))
      (node (ref "IC4") (pin "11") (pinfunction "V-_11") (pintype "power_in"))
      (node (ref "IC5") (pin "4") (pinfunction "V-_4") (pintype "power_in"))
      (node (ref "L1") (pin "2") (pinfunction "2_2") (pintype "passive"))
    )
    (net (code "3") (name "/ADC0") (class "Default")
      (node (ref "D5") (pin "1") (pinfunction "A_1") (pintype "passive"))
      (node (ref "IC2") (pin "8") (pinfunction "OUT_8") (pintype "output"))
      (node (ref "IC2") (pin "9") (pinfunction "-IN_9") (pintype "input"))
      (node (ref "JP6") (pin "4") (pinfunction "4_4") (pintype "passive"))
    )
    (net (code "4") (name "/ADC1") (class "Default")
      (node (ref "D4") (pin "1") (pinfunction "A_1") (pintype "passive"))
      (node (ref "IC2") (pin "6") (pinfunction "-IN_6") (pintype "input"))
      (node (ref "IC2") (pin "7") (pinfunction "OUT_7") (pintype "output"))
      (node (ref "JP6") (pin "3") (pinfunction "3_3") (pintype "passive"))
    )
    (net (code "5") (name "/ADC2") (class "Default")
      (node (ref "D6") (pin "1") (pinfunction "A_1") (pintype "passive"))
      (node (ref "IC1") (pin "8") (pinfunction "OUT_8") (pintype "output"))
      (node (ref "IC1") (pin "9") (pinfunction "-IN_9") (pintype "input"))
      (node (ref "JP6") (pin "6") (pinfunction "6_6") (pintype "passive"))
    )
    (net (code "6") (name "/ADC3") (class "Default")
      (node (ref "D1") (pin "1") (pinfunction "A_1") (pintype "passive"))
      (node (ref "IC1") (pin "13") (pinfunction "-IN_13") (pintype "input"))
      (node (ref "IC1") (pin "14") (pinfunction "OUT_14") (pintype "output"))
      (node (ref "JP6") (pin "5") (pinfunction "5_5") (pintype "passive"))
    )
    (net (code "7") (name "/ADC4") (class "Default")
      (node (ref "D2") (pin "1") (pinfunction "A_1") (pintype "passive"))
      (node (ref "IC2") (pin "13") (pinfunction "-IN_13") (pintype "input"))
      (node (ref "IC2") (pin "14") (pinfunction "OUT_14") (pintype "output"))
      (node (ref "JP6") (pin "7") (pinfunction "7_7") (pintype "passive"))
    )
    (net (code "8") (name "/ADC6") (class "Default")
      (node (ref "D7") (pin "1") (pinfunction "A_1") (pintype "passive"))
      (node (ref "IC2") (pin "1") (pinfunction "OUT_1") (pintype "output"))
      (node (ref "IC2") (pin "2") (pinfunction "-IN_2") (pintype "input"))
      (node (ref "JP6") (pin "9") (pinfunction "9_9") (pintype "passive"))
    )
    (net (code "9") (name "/ADC14") (class "Default")
      (node (ref "D9") (pin "1") (pinfunction "A_1") (pintype "passive"))
      (node (ref "IC1") (pin "6") (pinfunction "-IN_6") (pintype "input"))
      (node (ref "IC1") (pin "7") (pinfunction "OUT_7") (pintype "output"))
      (node (ref "JP6") (pin "11") (pinfunction "11_11") (pintype "passive"))
    )
    (net (code "10") (name "/AUDIOINR") (class "Default")
      (node (ref "J1") (pin "T") (pinfunction "T_T") (pintype "bidirectional"))
      (node (ref "JP13") (pin "1") (pinfunction "1_1") (pintype "passive"))
      (node (ref "R16") (pin "1") (pinfunction "1_1") (pintype "passive"))
    )
    (net (code "11") (name "/AUDIOOUTL") (class "Default")
      (node (ref "CH1_WET") (pin "1") (pinfunction "1_1") (pintype "passive"))
      (node (ref "IC4") (pin "5") (pinfunction "+IN_5") (pintype "input"))
      (node (ref "JP13") (pin "8") (pinfunction "8_8") (pintype "passive"))
    )
    (net (code "12") (name "/AUDIOOUTR") (class "Default")
      (node (ref "IC5") (pin "3") (pinfunction "+IN_3") (pintype "input"))
      (node (ref "JP13") (pin "7") (pinfunction "7_7") (pintype "passive"))
    )
    (net (code "13") (name "/D2_N") (class "Default")
      (node (ref "DM2") (pin "1") (pinfunction "1_1") (pintype "passive"))
      (node (ref "JP5") (pin "18") (pinfunction "18_18") (pintype "passive"))
      (node (ref "X2") (pin "2") (pinfunction "2_2") (pintype "passive"))
    )
    (net (code "14") (name "/D2_P") (class "Default")
      (node (ref "DP2") (pin "1") (pinfunction "1_1") (pintype "passive"))
      (node (ref "JP5") (pin "17") (pinfunction "17_17") (pintype "passive"))
      (node (ref "X2") (pin "3") (pinfunction "3_3") (pintype "passive"))
    )
    (net (code "15") (name "/MIC_OR_LINE_SIGNAL") (class "Default")
      (node (ref "CH1_DRY") (pin "1") (pinfunction "1_1") (pintype "passive"))
      (node (ref "IC13") (pin "1") (pinfunction "COM_1") (pintype "bidirectional"))
      (node (ref "IC4") (pin "3") (pinfunction "+IN_3") (pintype "input"))
      (node (ref "JP13") (pin "2") (pinfunction "2_2") (pintype "passive"))
      (node (ref "R4") (pin "1") (pinfunction "1_1") (pintype "passive"))
    )
    (net (code "16") (name "/MIC_SIGNAL") (class "Default")
      (node (ref "D10") (pin "1") (pinfunction "A_1") (pintype "passive"))
      (node (ref "IC13") (pin "8") (pinfunction "NO_8") (pintype "bidirectional"))
      (node (ref "IC3") (pin "6") (pinfunction "OUT_6") (pintype "output"))
      (node (ref "MIC_SIGNAL") (pin "1") (pinfunction "1_1") (pintype "passive"))
    )
    (net (code "17") (name "3V0") (class "Default")
      (node (ref "OLED1") (pin "P$5") (pinfunction "3.3V_P$5") (pintype "bidirectional"))
      (node (ref "R24") (pin "1") (pinfunction "1_1") (pintype "passive"))
      (node (ref "R25") (pin "1") (pinfunction "1_1") (pintype "passive"))
    )
    (net (code "18") (name "3V3") (class "Default")
      (node (ref "C1") (pin "1") (pinfunction "1_1") (pintype "passive"))
      (node (ref "C17") (pin "1") (pinfunction "1_1") (pintype "passive"))
      (node (ref "C18") (pin "1") (pinfunction "1_1") (pintype "passive"))
      (node (ref "C2") (pin "1") (pinfunction "1_1") (pintype "passive"))
      (node (ref "C26") (pin "1") (pinfunction "1_1") (pintype "passive"))
      (node (ref "C35") (pin "1") (pinfunction "1_1") (pintype "passive"))
      (node (ref "C4") (pin "1") (pinfunction "1_1") (pintype "passive"))
      (node (ref "D1") (pin "3") (pinfunction "C_3") (pintype "passive"))
      (node (ref "D10") (pin "3") (pinfunction "C_3") (pintype "passive"))
      (node (ref "D11") (pin "3") (pinfunction "C_3") (pintype "passive"))
      (node (ref "D2") (pin "3") (pinfunction "C_3") (pintype "passive"))
      (node (ref "D4") (pin "3") (pinfunction "C_3") (pintype "passive"))
      (node (ref "D5") (pin "3") (pinfunction "C_3") (pintype "passive"))
      (node (ref "D6") (pin "3") (pinfunction "C_3") (pintype "passive"))
      (node (ref "D7") (pin "3") (pinfunction "C_3") (pintype "passive"))
      (node (ref "D9") (pin "3") (pinfunction "C_3") (pintype "passive"))
      (node (ref "J9") (pin "R") (pinfunction "R_R") (pintype "bidirectional"))
      (node (ref "JP6") (pin "1") (pinfunction "1_1") (pintype "passive"))
      (node (ref "U$12") (pin "3-09") (pinfunction "3_3-09") (pintype "bidirectional"))
      (node (ref "U$16") (pin "3-09") (pinfunction "3_3-09") (pintype "bidirectional"))
      (node (ref "U$27") (pin "3-09") (pinfunction "3_3-09") (pintype "bidirectional"))
      (node (ref "U$28") (pin "3-09") (pinfunction "3_3-09") (pintype "bidirectional"))
      (node (ref "U$31") (pin "3-09") (pinfunction "3_3-09") (pintype "bidirectional"))
      (node (ref "U$32") (pin "3-09") (pinfunction "3_3-09") (pintype "bidirectional"))
    )
    (net (code "19") (name "5V0") (class "Default")
      (node (ref "C28") (pin "+") (pinfunction "+_+") (pintype "passive"))
      (node (ref "IC12") (pin "P$5") (pinfunction "OUT_P$5") (pintype "bidirectional"))
      (node (ref "JP5") (pin "20") (pinfunction "20_20") (pintype "passive"))
      (node (ref "OLED1") (pin "P$6") (pinfunction "VIN_P$6") (pintype "bidirectional"))
      (node (ref "X2") (pin "1") (pinfunction "1_1") (pintype "passive"))
    )
    (net (code "20") (name "9V0") (class "Default")
      (node (ref "C13") (pin "+") (pinfunction "+_+") (pintype "passive"))
      (node (ref "C14") (pin "1") (pinfunction "1_1") (pintype "passive"))
      (node (ref "C34") (pin "1") (pinfunction "1_1") (pintype "passive"))
      (node (ref "IC11") (pin "P$2") (pinfunction "IN_VCC_P$2") (pintype "bidirectional"))
      (node (ref "IC12") (pin "P$2") (pinfunction "IN_VCC_P$2") (pintype "bidirectional"))
      (node (ref "L5") (pin "2") (pinfunction "2_2") (pintype "passive"))
    )
    (net (code "21") (name "AGND") (class "Default")
      (node (ref "AGND3") (pin "1") (pinfunction "1_1") (pintype "passive"))
      (node (ref "AGND4") (pin "1") (pinfunction "1_1") (pintype "passive"))
      (node (ref "C1") (pin "2") (pinfunction "2_2") (pintype "passive"))
      (node (ref "C10") (pin "2") (pinfunction "2_2") (pintype "passive"))
      (node (ref "C11") (pin "2") (pinfunction "2_2") (pintype "passive"))
      (node (ref "C15") (pin "-") (pinfunction "-_-") (pintype "passive"))
      (node (ref "C16") (pin "+") (pinfunction "+_+") (pintype "passive"))
      (node (ref "C17") (pin "2") (pinfunction "2_2") (pintype "passive"))
      (node (ref "C18") (pin "2") (pinfunction "2_2") (pintype "passive"))
      (node (ref "C2") (pin "2") (pinfunction "2_2") (pintype "passive"))
      (node (ref "C22") (pin "2") (pinfunction "2_2") (pintype "passive"))
      (node (ref "C23") (pin "2") (pinfunction "2_2") (pintype "passive"))
      (node (ref "C24") (pin "2") (pinfunction "2_2") (pintype "passive"))
      (node (ref "C26") (pin "2") (pinfunction "2_2") (pintype "passive"))
      (node (ref "C3") (pin "2") (pinfunction "2_2") (pintype "passive"))
      (node (ref "C30") (pin "-") (pinfunction "-_-") (pintype "passive"))
      (node (ref "C31") (pin "+") (pinfunction "+_+") (pintype "passive"))
      (node (ref "C32") (pin "2") (pinfunction "2_2") (pintype "passive"))
      (node (ref "C35") (pin "2") (pinfunction "2_2") (pintype "passive"))
      (node (ref "C36") (pin "2") (pinfunction "2_2") (pintype "passive"))
      (node (ref "C37") (pin "2") (pinfunction "2_2") (pintype "passive"))
      (node (ref "C38") (pin "2") (pinfunction "2_2") (pintype "passive"))
      (node (ref "C4") (pin "2") (pinfunction "2_2") (pintype "passive"))
      (node (ref "C40") (pin "2") (pinfunction "2_2") (pintype "passive"))
      (node (ref "C41") (pin "1") (pinfunction "1_1") (pintype "passive"))
      (node (ref "C42") (pin "2") (pinfunction "2_2") (pintype "passive"))
      (node (ref "C44") (pin "1") (pinfunction "1_1") (pintype "passive"))
      (node (ref "C45") (pin "2") (pinfunction "2_2") (pintype "passive"))
      (node (ref "C48") (pin "2") (pinfunction "2_2") (pintype "passive"))
      (node (ref "C49") (pin "1") (pinfunction "1_1") (pintype "passive"))
      (node (ref "C5") (pin "1") (pinfunction "1_1") (pintype "passive"))
      (node (ref "C50") (pin "-") (pinfunction "-_-") (pintype "passive"))
      (node (ref "C51") (pin "2") (pinfunction "2_2") (pintype "passive"))
      (node (ref "C52") (pin "1") (pinfunction "1_1") (pintype "passive"))
      (node (ref "C6") (pin "2") (pinfunction "2_2") (pintype "passive"))
      (node (ref "C7") (pin "1") (pinfunction "1_1") (pintype "passive"))
      (node (ref "C8") (pin "2") (pinfunction "2_2") (pintype "passive"))
      (node (ref "C9") (pin "1") (pinfunction "1_1") (pintype "passive"))
      (node (ref "D14") (pin "1") (pinfunction "A_1") (pintype "passive"))
      (node (ref "D15") (pin "1") (pinfunction "A_1") (pintype "passive"))
      (node (ref "D16") (pin "1") (pinfunction "A_1") (pintype "passive"))
      (node (ref "D3") (pin "1") (pinfunction "A_1") (pintype "passive"))
      (node (ref "IC1") (pin "3") (pinfunction "+IN_3") (pintype "input"))
      (node (ref "IC11") (pin "P$6") (pinfunction "OUTGND_P$6") (pintype "bidirectional"))
      (node (ref "IC13") (pin "3") (pinfunction "GND_3") (pintype "bidirectional"))
      (node (ref "IC3") (pin "5") (pinfunction "REF_5") (pintype "passive"))
      (node (ref "IC4") (pin "10") (pinfunction "+IN_10") (pintype "input"))
      (node (ref "IC4") (pin "12") (pinfunction "+IN_12") (pintype "input"))
      (node (ref "J1") (pin "S") (pinfunction "S_S") (pintype "bidirectional"))
      (node (ref "J3") (pin "S") (pinfunction "S_S") (pintype "bidirectional"))
      (node (ref "J4") (pin "S") (pinfunction "S_S") (pintype "bidirectional"))
      (node (ref "J9") (pin "S") (pinfunction "S_S") (pintype "bidirectional"))
      (node (ref "JP13") (pin "3") (pinfunction "3_3") (pintype "passive"))
      (node (ref "JP13") (pin "4") (pinfunction "4_4") (pintype "passive"))
      (node (ref "JP13") (pin "5") (pinfunction "5_5") (pintype "passive"))
      (node (ref "JP13") (pin "6") (pinfunction "6_6") (pintype "passive"))
      (node (ref "JP6") (pin "2") (pinfunction "2_2") (pintype "passive"))
      (node (ref "R10") (pin "1") (pinfunction "1_1") (pintype "passive"))
      (node (ref "R12") (pin "1") (pinfunction "1_1") (pintype "passive"))
      (node (ref "R14") (pin "1") (pinfunction "1_1") (pintype "passive"))
      (node (ref "R17") (pin "1") (pinfunction "1_1") (pintype "passive"))
      (node (ref "R18") (pin "1") (pinfunction "1_1") (pintype "passive"))
      (node (ref "R2") (pin "1") (pinfunction "1_1") (pintype "passive"))
      (node (ref "R26") (pin "2") (pinfunction "2_2") (pintype "passive"))
      (node (ref "R29") (pin "1") (pinfunction "1_1") (pintype "passive"))
      (node (ref "R3") (pin "1") (pinfunction "1_1") (pintype "passive"))
      (node (ref "R30") (pin "1") (pinfunction "1_1") (pintype "passive"))
      (node (ref "R42") (pin "1") (pinfunction "1_1") (pintype "passive"))
      (node (ref "R45") (pin "1") (pinfunction "1_1") (pintype "passive"))
      (node (ref "R63") (pin "1") (pinfunction "1_1") (pintype "passive"))
      (node (ref "R7") (pin "1") (pinfunction "1_1") (pintype "passive"))
      (node (ref "R9") (pin "1") (pinfunction "1_1") (pintype "passive"))
      (node (ref "S12") (pin "1") (pinfunction "S_1") (pintype "passive"))
      (node (ref "T1") (pin "E") (pinfunction "E_E") (pintype "passive"))
      (node (ref "T14") (pin "E") (pinfunction "E_E") (pintype "passive"))
      (node (ref "T2") (pin "E") (pinfunction "E_E") (pintype "passive"))
      (node (ref "T3") (pin "E") (pinfunction "E_E") (pintype "passive"))
      (node (ref "U$12") (pin "1-09") (pinfunction "1_1-09") (pintype "bidirectional"))
      (node (ref "U$14") (pin "2-09") (pinfunction "2_2-09") (pintype "bidirectional"))
      (node (ref "U$16") (pin "1-09") (pinfunction "1_1-09") (pintype "bidirectional"))
      (node (ref "U$27") (pin "1-09") (pinfunction "1_1-09") (pintype "bidirectional"))
      (node (ref "U$28") (pin "1-09") (pinfunction "1_1-09") (pintype "bidirectional"))
      (node (ref "U$31") (pin "1-09") (pinfunction "1_1-09") (pintype "bidirectional"))
      (node (ref "U$32") (pin "1-09") (pinfunction "1_1-09") (pintype "bidirectional"))
      (node (ref "X1") (pin "1") (pinfunction "1_1") (pintype "passive"))
      (node (ref "X1") (pin "G") (pinfunction "G_G") (pintype "passive"))
      (node (ref "X1") (pin "S") (pinfunction "S_S") (pintype "passive"))
    )
    (net (code "22") (name "DGND") (class "Default")
      (node (ref "C13") (pin "-") (pinfunction "-_-") (pintype "passive"))
      (node (ref "C14") (pin "2") (pinfunction "2_2") (pintype "passive"))
      (node (ref "C27") (pin "-") (pinfunction "-_-") (pintype "passive"))
      (node (ref "C28") (pin "-") (pinfunction "-_-") (pintype "passive"))
      (node (ref "C29") (pin "-") (pinfunction "-_-") (pintype "passive"))
      (node (ref "C34") (pin "2") (pinfunction "2_2") (pintype "passive"))
      (node (ref "DGND1") (pin "1") (pinfunction "1_1") (pintype "passive"))
      (node (ref "IC11") (pin "P$1") (pinfunction "IN_GND_P$1") (pintype "bidirectional"))
      (node (ref "IC12") (pin "P$1") (pinfunction "IN_GND_P$1") (pintype "bidirectional"))
      (node (ref "IC12") (pin "P$6") (pinfunction "OUT_GND_P$6") (pintype "bidirectional"))
      (node (ref "J10") (pin "2") (pinfunction "SHEILD_2") (pintype "bidirectional"))
      (node (ref "JP20") (pin "1") (pinfunction "1_1") (pintype "passive"))
      (node (ref "JP5") (pin "19") (pinfunction "19_19") (pintype "passive"))
      (node (ref "LED1") (pin "C") (pinfunction "C_C") (pintype "passive"))
      (node (ref "LED12") (pin "C") (pinfunction "C_C") (pintype "passive"))
      (node (ref "LED13") (pin "C") (pinfunction "C_C") (pintype "passive"))
      (node (ref "LED15") (pin "C") (pinfunction "C_C") (pintype "passive"))
      (node (ref "LED17") (pin "C") (pinfunction "C_C") (pintype "passive"))
      (node (ref "LED2") (pin "C") (pinfunction "C_C") (pintype "passive"))
      (node (ref "LED4") (pin "C") (pinfunction "C_C") (pintype "passive"))
      (node (ref "LED5") (pin "C") (pinfunction "C_C") (pintype "passive"))
      (node (ref "LED6") (pin "C") (pinfunction "C_C") (pintype "passive"))
      (node (ref "LED7") (pin "C") (pinfunction "C_C") (pintype "passive"))
      (node (ref "LED9") (pin "C") (pinfunction "C_C") (pintype "passive"))
      (node (ref "OLED1") (pin "P$4") (pinfunction "GND_P$4") (pintype "bidirectional"))
      (node (ref "U$11") (pin "P1_1") (pinfunction "P$1_P1_1") (pintype "bidirectional"))
      (node (ref "U$11") (pin "P1_2") (pinfunction "P$2_P1_2") (pintype "bidirectional"))
      (node (ref "U$11") (pin "P1_3") (pinfunction "P$3_P1_3") (pintype "bidirectional"))
      (node (ref "U$33") (pin "P1_1") (pinfunction "P$1_P1_1") (pintype "bidirectional"))
      (node (ref "U$33") (pin "P1_2") (pinfunction "P$2_P1_2") (pintype "bidirectional"))
      (node (ref "U$33") (pin "P1_3") (pinfunction "P$3_P1_3") (pintype "bidirectional"))
      (node (ref "U$39") (pin "P1_1") (pinfunction "P$1_P1_1") (pintype "bidirectional"))
      (node (ref "U$39") (pin "P1_2") (pinfunction "P$2_P1_2") (pintype "bidirectional"))
      (node (ref "U$39") (pin "P1_3") (pinfunction "P$3_P1_3") (pintype "bidirectional"))
      (node (ref "U$40") (pin "P1_1") (pinfunction "P$1_P1_1") (pintype "bidirectional"))
      (node (ref "U$40") (pin "P1_2") (pinfunction "P$2_P1_2") (pintype "bidirectional"))
      (node (ref "U$40") (pin "P1_3") (pinfunction "P$3_P1_3") (pintype "bidirectional"))
      (node (ref "U$42") (pin "P1_1") (pinfunction "P$1_P1_1") (pintype "bidirectional"))
      (node (ref "U$42") (pin "P1_2") (pinfunction "P$2_P1_2") (pintype "bidirectional"))
      (node (ref "U$42") (pin "P1_3") (pinfunction "P$3_P1_3") (pintype "bidirectional"))
      (node (ref "U$43") (pin "P1_1") (pinfunction "P$1_P1_1") (pintype "bidirectional"))
      (node (ref "U$43") (pin "P1_2") (pinfunction "P$2_P1_2") (pintype "bidirectional"))
      (node (ref "U$43") (pin "P1_3") (pinfunction "P$3_P1_3") (pintype "bidirectional"))
      (node (ref "U$44") (pin "P1_1") (pinfunction "P$1_P1_1") (pintype "bidirectional"))
      (node (ref "U$44") (pin "P1_2") (pinfunction "P$2_P1_2") (pintype "bidirectional"))
      (node (ref "U$44") (pin "P1_3") (pinfunction "P$3_P1_3") (pintype "bidirectional"))
      (node (ref "U$45") (pin "P1_1") (pinfunction "P$1_P1_1") (pintype "bidirectional"))
      (node (ref "U$45") (pin "P1_2") (pinfunction "P$2_P1_2") (pintype "bidirectional"))
      (node (ref "U$45") (pin "P1_3") (pinfunction "P$3_P1_3") (pintype "bidirectional"))
      (node (ref "U$48") (pin "P1_1") (pinfunction "P$1_P1_1") (pintype "bidirectional"))
      (node (ref "U$48") (pin "P1_2") (pinfunction "P$2_P1_2") (pintype "bidirectional"))
      (node (ref "U$48") (pin "P1_3") (pinfunction "P$3_P1_3") (pintype "bidirectional"))
      (node (ref "U$7") (pin "P1_1") (pinfunction "P$1_P1_1") (pintype "bidirectional"))
      (node (ref "U$7") (pin "P1_2") (pinfunction "P$2_P1_2") (pintype "bidirectional"))
      (node (ref "U$7") (pin "P1_3") (pinfunction "P$3_P1_3") (pintype "bidirectional"))
      (node (ref "X2") (pin "4") (pinfunction "4_4") (pintype "passive"))
    )
    (net (code "23") (name "Net-(C12-Pad+)") (class "Default")
      (node (ref "C12") (pin "+") (pinfunction "+_+") (pintype "passive"))
      (node (ref "C20") (pin "1") (pinfunction "1_1") (pintype "passive"))
      (node (ref "R43") (pin "2") (pinfunction "2_2") (pintype "passive"))
      (node (ref "X1") (pin "2") (pinfunction "2_2") (pintype "passive"))
    )
    (net (code "24") (name "Net-(C19-Pad+)") (class "Default")
      (node (ref "C19") (pin "+") (pinfunction "+_+") (pintype "passive"))
      (node (ref "C21") (pin "2") (pinfunction "2_2") (pintype "passive"))
      (node (ref "R44") (pin "2") (pinfunction "2_2") (pintype "passive"))
      (node (ref "X1") (pin "3") (pinfunction "3_3") (pintype "passive"))
    )
    (net (code "25") (name "Net-(C20-Pad2)") (class "Default")
      (node (ref "C20") (pin "2") (pinfunction "2_2") (pintype "passive"))
      (node (ref "C21") (pin "1") (pinfunction "1_1") (pintype "passive"))
      (node (ref "C22") (pin "1") (pinfunction "1_1") (pintype "passive"))
    )
    (net (code "26") (name "Net-(C33-Pad+)") (class "Default")
      (node (ref "C33") (pin "+") (pinfunction "+_+") (pintype "passive"))
      (node (ref "R19") (pin "2") (pinfunction "2_2") (pintype "passive"))
      (node (ref "R20") (pin "2") (pinfunction "2_2") (pintype "passive"))
      (node (ref "R21") (pin "2") (pinfunction "2_2") (pintype "passive"))
      (node (ref "R33") (pin "2") (pinfunction "2_2") (pintype "passive"))
      (node (ref "R34") (pin "2") (pinfunction "2_2") (pintype "passive"))
      (node (ref "R35") (pin "2") (pinfunction "2_2") (pintype "passive"))
      (node (ref "R36") (pin "2") (pinfunction "2_2") (pintype "passive"))
      (node (ref "R37") (pin "2") (pinfunction "2_2") (pintype "passive"))
      (node (ref "R38") (pin "2") (pinfunction "2_2") (pintype "passive"))
      (node (ref "R5") (pin "2") (pinfunction "2_2") (pintype "passive"))
      (node (ref "R6") (pin "2") (pinfunction "2_2") (pintype "passive"))
      (node (ref "U$1") (pin "1") (pinfunction "1_1") (pintype "bidirectional"))
    )
    (net (code "27") (name "Net-(C46-Pad1)") (class "Default")
      (node (ref "C46") (pin "1") (pinfunction "1_1") (pintype "passive"))
      (node (ref "R28") (pin "2") (pinfunction "2_2") (pintype "passive"))
    )
    (net (code "28") (name "Net-(C46-Pad2)") (class "Default")
      (node (ref "C46") (pin "2") (pinfunction "2_2") (pintype "passive"))
      (node (ref "J3") (pin "R") (pinfunction "R_R") (pintype "bidirectional"))
      (node (ref "R29") (pin "2") (pinfunction "2_2") (pintype "passive"))
    )
    (net (code "29") (name "Net-(C47-Pad1)") (class "Default")
      (node (ref "C47") (pin "1") (pinfunction "1_1") (pintype "passive"))
      (node (ref "R31") (pin "2") (pinfunction "2_2") (pintype "passive"))
    )
    (net (code "30") (name "Net-(C47-Pad2)") (class "Default")
      (node (ref "C47") (pin "2") (pinfunction "2_2") (pintype "passive"))
      (node (ref "J4") (pin "R") (pinfunction "R_R") (pintype "bidirectional"))
      (node (ref "R30") (pin "2") (pinfunction "2_2") (pintype "passive"))
    )
    (net (code "31") (name "Net-(D3-C)") (class "Default")
      (node (ref "D3") (pin "3") (pinfunction "C_3") (pintype "passive"))
      (node (ref "R39") (pin "2") (pinfunction "2_2") (pintype "passive"))
      (node (ref "T14") (pin "B") (pinfunction "B_B") (pintype "passive"))
    )
    (net (code "32") (name "Net-(D11-A)") (class "Default")
      (node (ref "D11") (pin "1") (pinfunction "A_1") (pintype "passive"))
      (node (ref "IC13") (pin "2") (pinfunction "NC_2") (pintype "bidirectional"))
      (node (ref "X1") (pin "T") (pinfunction "T_T") (pintype "passive"))
    )
    (net (code "33") (name "Net-(D14-C)") (class "Default")
      (node (ref "D14") (pin "3") (pinfunction "C_3") (pintype "passive"))
      (node (ref "R41") (pin "2") (pinfunction "2_2") (pintype "passive"))
      (node (ref "T1") (pin "B") (pinfunction "B_B") (pintype "passive"))
    )
    (net (code "34") (name "Net-(D15-C)") (class "Default")
      (node (ref "D15") (pin "3") (pinfunction "C_3") (pintype "passive"))
      (node (ref "R16") (pin "2") (pinfunction "2_2") (pintype "passive"))
      (node (ref "T3") (pin "B") (pinfunction "B_B") (pintype "passive"))
    )
    (net (code "35") (name "Net-(D16-C)") (class "Default")
      (node (ref "D16") (pin "3") (pinfunction "C_3") (pintype "passive"))
      (node (ref "R4") (pin "2") (pinfunction "2_2") (pintype "passive"))
      (node (ref "T2") (pin "B") (pinfunction "B_B") (pintype "passive"))
    )
    (net (code "36") (name "Net-(GPIO-Pad1)") (class "Default")
      (node (ref "GPIO") (pin "1") (pinfunction "1_1") (pintype "passive"))
      (node (ref "JP6") (pin "16") (pinfunction "16_16") (pintype "passive"))
    )
    (net (code "37") (name "Net-(IC1A--IN)") (class "Default")
      (node (ref "IC1") (pin "1") (pinfunction "OUT_1") (pintype "output"))
      (node (ref "IC1") (pin "2") (pinfunction "-IN_2") (pintype "input"))
    )
    (net (code "38") (name "Net-(IC1B-+IN)") (class "Default")
      (node (ref "C45") (pin "1") (pinfunction "1_1") (pintype "passive"))
      (node (ref "IC1") (pin "5") (pinfunction "+IN_5") (pintype "input"))
      (node (ref "J9") (pin "T") (pinfunction "T_T") (pintype "bidirectional"))
      (node (ref "R14") (pin "2") (pinfunction "2_2") (pintype "passive"))
    )
    (net (code "39") (name "Net-(IC1C-+IN)") (class "Default")
      (node (ref "C36") (pin "1") (pinfunction "1_1") (pintype "passive"))
      (node (ref "IC1") (pin "10") (pinfunction "+IN_10") (pintype "input"))
      (node (ref "R63") (pin "2") (pinfunction "2_2") (pintype "passive"))
      (node (ref "U$16") (pin "2-09") (pinfunction "2_2-09") (pintype "bidirectional"))
    )
    (net (code "40") (name "Net-(IC1D-+IN)") (class "Default")
      (node (ref "C10") (pin "1") (pinfunction "1_1") (pintype "passive"))
      (node (ref "IC1") (pin "12") (pinfunction "+IN_12") (pintype "input"))
      (node (ref "R10") (pin "2") (pinfunction "2_2") (pintype "passive"))
      (node (ref "U$12") (pin "2-09") (pinfunction "2_2-09") (pintype "bidirectional"))
    )
    (net (code "41") (name "Net-(IC2A-+IN)") (class "Default")
      (node (ref "C32") (pin "1") (pinfunction "1_1") (pintype "passive"))
      (node (ref "IC2") (pin "3") (pinfunction "+IN_3") (pintype "input"))
      (node (ref "R3") (pin "2") (pinfunction "2_2") (pintype "passive"))
      (node (ref "U$32") (pin "2-09") (pinfunction "2_2-09") (pintype "bidirectional"))
    )
    (net (code "42") (name "Net-(IC2B-+IN)") (class "Default")
      (node (ref "C38") (pin "1") (pinfunction "1_1") (pintype "passive"))
      (node (ref "IC2") (pin "5") (pinfunction "+IN_5") (pintype "input"))
      (node (ref "R17") (pin "2") (pinfunction "2_2") (pintype "passive"))
      (node (ref "U$28") (pin "2-09") (pinfunction "2_2-09") (pintype "bidirectional"))
    )
    (net (code "43") (name "Net-(IC2C-+IN)") (class "Default")
      (node (ref "C42") (pin "1") (pinfunction "1_1") (pintype "passive"))
      (node (ref "IC2") (pin "10") (pinfunction "+IN_10") (pintype "input"))
      (node (ref "R18") (pin "2") (pinfunction "2_2") (pintype "passive"))
      (node (ref "U$27") (pin "2-09") (pinfunction "2_2-09") (pintype "bidirectional"))
    )
    (net (code "44") (name "Net-(IC2D-+IN)") (class "Default")
      (node (ref "C11") (pin "1") (pinfunction "1_1") (pintype "passive"))
      (node (ref "IC2") (pin "12") (pinfunction "+IN_12") (pintype "input"))
      (node (ref "R2") (pin "2") (pinfunction "2_2") (pintype "passive"))
      (node (ref "U$31") (pin "2-09") (pinfunction "2_2-09") (pintype "bidirectional"))
    )
    (net (code "45") (name "Net-(IC3-+IN)") (class "Default")
      (node (ref "C19") (pin "-") (pinfunction "-_-") (pintype "passive"))
      (node (ref "C24") (pin "1") (pinfunction "1_1") (pintype "passive"))
      (node (ref "C25") (pin "2") (pinfunction "2_2") (pintype "passive"))
      (node (ref "IC3") (pin "3") (pinfunction "+IN_3") (pintype "input"))
      (node (ref "R12") (pin "2") (pinfunction "2_2") (pintype "passive"))
    )
    (net (code "46") (name "Net-(IC3--IN)") (class "Default")
      (node (ref "C12") (pin "-") (pinfunction "-_-") (pintype "passive"))
      (node (ref "C23") (pin "1") (pinfunction "1_1") (pintype "passive"))
      (node (ref "C25") (pin "1") (pinfunction "1_1") (pintype "passive"))
      (node (ref "IC3") (pin "2") (pinfunction "-IN_2") (pintype "input"))
      (node (ref "R9") (pin "2") (pinfunction "2_2") (pintype "passive"))
    )
    (net (code "47") (name "Net-(IC3-RG1)") (class "Default")
      (node (ref "IC3") (pin "1") (pinfunction "RG1_1") (pintype "passive"))
      (node (ref "R13") (pin "2") (pinfunction "2_2") (pintype "passive"))
    )
    (net (code "48") (name "Net-(IC3-RG2)") (class "Default")
      (node (ref "C33") (pin "-") (pinfunction "-_-") (pintype "passive"))
      (node (ref "IC3") (pin "8") (pinfunction "RG2_8") (pintype "passive"))
    )
    (net (code "49") (name "Net-(IC4A--IN)") (class "Default")
      (node (ref "IC4") (pin "1") (pinfunction "OUT_1") (pintype "output"))
      (node (ref "IC4") (pin "2") (pinfunction "-IN_2") (pintype "input"))
      (node (ref "R46") (pin "2") (pinfunction "2_2") (pintype "passive"))
    )
    (net (code "50") (name "Net-(IC4B--IN)") (class "Default")
      (node (ref "IC4") (pin "6") (pinfunction "-IN_6") (pintype "input"))
      (node (ref "IC4") (pin "7") (pinfunction "OUT_7") (pintype "output"))
      (node (ref "R47") (pin "2") (pinfunction "2_2") (pintype "passive"))
    )
    (net (code "51") (name "Net-(IC4C--IN)") (class "Default")
      (node (ref "IC4") (pin "9") (pinfunction "-IN_9") (pintype "input"))
      (node (ref "R48") (pin "1") (pinfunction "1_1") (pintype "passive"))
      (node (ref "R49") (pin "1") (pinfunction "1_1") (pintype "passive"))
      (node (ref "R50") (pin "2") (pinfunction "2_2") (pintype "passive"))
    )
    (net (code "52") (name "Net-(IC4C-OUT)") (class "Default")
      (node (ref "IC4") (pin "8") (pinfunction "OUT_8") (pintype "output"))
      (node (ref "R50") (pin "1") (pinfunction "1_1") (pintype "passive"))
      (node (ref "R51") (pin "2") (pinfunction "2_2") (pintype "passive"))
    )
    (net (code "53") (name "Net-(IC4D--IN)") (class "Default")
      (node (ref "IC4") (pin "13") (pinfunction "-IN_13") (pintype "input"))
      (node (ref "R51") (pin "1") (pinfunction "1_1") (pintype "passive"))
      (node (ref "R52") (pin "2") (pinfunction "2_2") (pintype "passive"))
    )
    (net (code "54") (name "Net-(IC4D-OUT)") (class "Default")
      (node (ref "CH1_OUT") (pin "1") (pinfunction "1_1") (pintype "passive"))
      (node (ref "IC4") (pin "14") (pinfunction "OUT_14") (pintype "output"))
      (node (ref "IC5") (pin "5") (pinfunction "+IN_5") (pintype "input"))
      (node (ref "R52") (pin "1") (pinfunction "1_1") (pintype "passive"))
    )
    (net (code "55") (name "Net-(IC5A--IN)") (class "Default")
      (node (ref "IC5") (pin "2") (pinfunction "-IN_2") (pintype "input"))
      (node (ref "R7") (pin "2") (pinfunction "2_2") (pintype "passive"))
      (node (ref "R8") (pin "2") (pinfunction "2_2") (pintype "passive"))
    )
    (net (code "56") (name "Net-(IC5A-OUT)") (class "Default")
      (node (ref "IC5") (pin "1") (pinfunction "OUT_1") (pintype "output"))
      (node (ref "R27") (pin "2") (pinfunction "2_2") (pintype "passive"))
      (node (ref "R8") (pin "1") (pinfunction "1_1") (pintype "passive"))
    )
    (net (code "57") (name "Net-(IC5B--IN)") (class "Default")
      (node (ref "IC5") (pin "6") (pinfunction "-IN_6") (pintype "input"))
      (node (ref "R22") (pin "2") (pinfunction "2_2") (pintype "passive"))
      (node (ref "R26") (pin "1") (pinfunction "1_1") (pintype "passive"))
    )
    (net (code "58") (name "Net-(IC5B-OUT)") (class "Default")
      (node (ref "IC5") (pin "7") (pinfunction "OUT_7") (pintype "output"))
      (node (ref "R22") (pin "1") (pinfunction "1_1") (pintype "passive"))
      (node (ref "R32") (pin "2") (pinfunction "2_2") (pintype "passive"))
    )
    (net (code "59") (name "Net-(IC11-OUT+)") (class "Default")
      (node (ref "IC11") (pin "P$5") (pinfunction "OUT+_P$5") (pintype "bidirectional"))
      (node (ref "L2") (pin "1") (pinfunction "1_1") (pintype "passive"))
    )
    (net (code "60") (name "Net-(IC11-OUT-)") (class "Default")
      (node (ref "IC11") (pin "P$7") (pinfunction "OUT-_P$7") (pintype "bidirectional"))
      (node (ref "L1") (pin "1") (pinfunction "1_1") (pintype "passive"))
    )
    (net (code "61") (name "Net-(IC12-CS)") (class "Default")
      (node (ref "C29") (pin "+") (pinfunction "+_+") (pintype "passive"))
      (node (ref "IC12") (pin "P$7") (pinfunction "CS_P$7") (pintype "bidirectional"))
    )
    (net (code "62") (name "Net-(IC13-IN)") (class "Default")
      (node (ref "IC13") (pin "6") (pinfunction "IN_6") (pintype "bidirectional"))
      (node (ref "R23") (pin "1") (pinfunction "1_1") (pintype "passive"))
      (node (ref "X1") (pin "SS") (pinfunction "SS_SS") (pintype "passive"))
    )
    (net (code "63") (name "Net-(J3-PadT)") (class "Default")
      (node (ref "J3") (pin "T") (pinfunction "T_T") (pintype "bidirectional"))
      (node (ref "R27") (pin "1") (pinfunction "1_1") (pintype "passive"))
      (node (ref "R28") (pin "1") (pinfunction "1_1") (pintype "passive"))
      (node (ref "R39") (pin "1") (pinfunction "1_1") (pintype "passive"))
    )
    (net (code "64") (name "Net-(J4-PadT)") (class "Default")
      (node (ref "J4") (pin "T") (pinfunction "T_T") (pintype "bidirectional"))
      (node (ref "R31") (pin "1") (pinfunction "1_1") (pintype "passive"))
      (node (ref "R32") (pin "1") (pinfunction "1_1") (pintype "passive"))
      (node (ref "R41") (pin "1") (pinfunction "1_1") (pintype "passive"))
    )
    (net (code "65") (name "Net-(J10-TIP)") (class "Default")
      (node (ref "C27") (pin "+") (pinfunction "+_+") (pintype "passive"))
      (node (ref "J10") (pin "1") (pinfunction "TIP_1") (pintype "bidirectional"))
      (node (ref "L5") (pin "1") (pinfunction "1_1") (pintype "passive"))
    )
    (net (code "66") (name "Net-(JP5-Pad9)") (class "Default")
      (node (ref "JP5") (pin "9") (pinfunction "9_9") (pintype "passive"))
      (node (ref "R11") (pin "1") (pinfunction "1_1") (pintype "passive"))
    )
    (net (code "67") (name "Net-(JP5-Pad11)") (class "Default")
      (node (ref "JP5") (pin "11") (pinfunction "11_11") (pintype "passive"))
      (node (ref "R55") (pin "1") (pinfunction "1_1") (pintype "passive"))
    )
    (net (code "68") (name "Net-(JP5-Pad12)") (class "Default")
      (node (ref "JP5") (pin "12") (pinfunction "12_12") (pintype "passive"))
      (node (ref "R54") (pin "1") (pinfunction "1_1") (pintype "passive"))
    )
    (net (code "69") (name "Net-(JP5-Pad13)") (class "Default")
      (node (ref "JP5") (pin "13") (pinfunction "13_13") (pintype "passive"))
      (node (ref "R56") (pin "1") (pinfunction "1_1") (pintype "passive"))
    )
    (net (code "70") (name "Net-(JP5-Pad14)") (class "Default")
      (node (ref "JP5") (pin "14") (pinfunction "14_14") (pintype "passive"))
      (node (ref "R53") (pin "1") (pinfunction "1_1") (pintype "passive"))
    )
    (net (code "71") (name "Net-(JP5-Pad15)") (class "Default")
      (node (ref "JP5") (pin "15") (pinfunction "15_15") (pintype "passive"))
      (node (ref "R57") (pin "1") (pinfunction "1_1") (pintype "passive"))
    )
    (net (code "72") (name "Net-(JP6-Pad8)") (class "Default")
      (node (ref "JP6") (pin "8") (pinfunction "8_8") (pintype "passive"))
      (node (ref "R62") (pin "1") (pinfunction "1_1") (pintype "passive"))
    )
    (net (code "73") (name "Net-(JP6-Pad10)") (class "Default")
      (node (ref "JP6") (pin "10") (pinfunction "10_10") (pintype "passive"))
      (node (ref "R61") (pin "1") (pinfunction "1_1") (pintype "passive"))
    )
    (net (code "74") (name "Net-(JP6-Pad12)") (class "Default")
      (node (ref "JP6") (pin "12") (pinfunction "12_12") (pintype "passive"))
      (node (ref "R60") (pin "1") (pinfunction "1_1") (pintype "passive"))
    )
    (net (code "75") (name "Net-(JP6-Pad14)") (class "Default")
      (node (ref "JP6") (pin "14") (pinfunction "14_14") (pintype "passive"))
      (node (ref "R59") (pin "1") (pinfunction "1_1") (pintype "passive"))
    )
    (net (code "76") (name "Net-(JP6-Pad17)") (class "Default")
      (node (ref "JP6") (pin "17") (pinfunction "17_17") (pintype "passive"))
      (node (ref "R58") (pin "1") (pinfunction "1_1") (pintype "passive"))
    )
    (net (code "77") (name "Net-(LED1-PadA)") (class "Default")
      (node (ref "LED1") (pin "A") (pinfunction "A_A") (pintype "passive"))
      (node (ref "R11") (pin "2") (pinfunction "2_2") (pintype "passive"))
    )
    (net (code "78") (name "Net-(LED2-PadA)") (class "Default")
      (node (ref "LED2") (pin "A") (pinfunction "A_A") (pintype "passive"))
      (node (ref "R53") (pin "2") (pinfunction "2_2") (pintype "passive"))
    )
    (net (code "79") (name "Net-(LED4-PadA)") (class "Default")
      (node (ref "LED4") (pin "A") (pinfunction "A_A") (pintype "passive"))
      (node (ref "R54") (pin "2") (pinfunction "2_2") (pintype "passive"))
    )
    (net (code "80") (name "Net-(LED5-PadA)") (class "Default")
      (node (ref "LED5") (pin "A") (pinfunction "A_A") (pintype "passive"))
      (node (ref "R55") (pin "2") (pinfunction "2_2") (pintype "passive"))
    )
    (net (code "81") (name "Net-(LED6-PadA)") (class "Default")
      (node (ref "LED6") (pin "A") (pinfunction "A_A") (pintype "passive"))
      (node (ref "R56") (pin "2") (pinfunction "2_2") (pintype "passive"))
    )
    (net (code "82") (name "Net-(LED7-PadA)") (class "Default")
      (node (ref "LED7") (pin "A") (pinfunction "A_A") (pintype "passive"))
      (node (ref "R57") (pin "2") (pinfunction "2_2") (pintype "passive"))
    )
    (net (code "83") (name "Net-(LED8-PadC)") (class "Default")
      (node (ref "LED8") (pin "C") (pinfunction "C_C") (pintype "passive"))
      (node (ref "R45") (pin "2") (pinfunction "2_2") (pintype "passive"))
    )
    (net (code "84") (name "Net-(LED9-PadA)") (class "Default")
      (node (ref "LED9") (pin "A") (pinfunction "A_A") (pintype "passive"))
      (node (ref "R58") (pin "2") (pinfunction "2_2") (pintype "passive"))
    )
    (net (code "85") (name "Net-(LED10-PadA)") (class "Default")
      (node (ref "LED10") (pin "A") (pinfunction "A_A") (pintype "passive"))
      (node (ref "R1") (pin "2") (pinfunction "2_2") (pintype "passive"))
    )
    (net (code "86") (name "Net-(LED10-PadC)") (class "Default")
      (node (ref "LED10") (pin "C") (pinfunction "C_C") (pintype "passive"))
      (node (ref "T2") (pin "C") (pinfunction "C_C") (pintype "passive"))
    )
    (net (code "87") (name "Net-(LED11-PadA)") (class "Default")
      (node (ref "LED11") (pin "A") (pinfunction "A_A") (pintype "passive"))
      (node (ref "R15") (pin "2") (pinfunction "2_2") (pintype "passive"))
    )
    (net (code "88") (name "Net-(LED11-PadC)") (class "Default")
      (node (ref "LED11") (pin "C") (pinfunction "C_C") (pintype "passive"))
      (node (ref "T3") (pin "C") (pinfunction "C_C") (pintype "passive"))
    )
    (net (code "89") (name "Net-(LED12-PadA)") (class "Default")
      (node (ref "LED12") (pin "A") (pinfunction "A_A") (pintype "passive"))
      (node (ref "R59") (pin "2") (pinfunction "2_2") (pintype "passive"))
    )
    (net (code "90") (name "Net-(LED13-PadA)") (class "Default")
      (node (ref "LED13") (pin "A") (pinfunction "A_A") (pintype "passive"))
      (node (ref "R60") (pin "2") (pinfunction "2_2") (pintype "passive"))
    )
    (net (code "91") (name "Net-(LED14-PadA)") (class "Default")
      (node (ref "LED14") (pin "A") (pinfunction "A_A") (pintype "passive"))
      (node (ref "R40") (pin "2") (pinfunction "2_2") (pintype "passive"))
    )
    (net (code "92") (name "Net-(LED14-PadC)") (class "Default")
      (node (ref "LED14") (pin "C") (pinfunction "C_C") (pintype "passive"))
      (node (ref "T1") (pin "C") (pinfunction "C_C") (pintype "passive"))
    )
    (net (code "93") (name "Net-(LED15-PadA)") (class "Default")
      (node (ref "LED15") (pin "A") (pinfunction "A_A") (pintype "passive"))
      (node (ref "R61") (pin "2") (pinfunction "2_2") (pintype "passive"))
    )
    (net (code "94") (name "Net-(LED16-PadA)") (class "Default")
      (node (ref "LED16") (pin "A") (pinfunction "A_A") (pintype "passive"))
      (node (ref "R65") (pin "2") (pinfunction "2_2") (pintype "passive"))
    )
    (net (code "95") (name "Net-(LED16-PadC)") (class "Default")
      (node (ref "LED16") (pin "C") (pinfunction "C_C") (pintype "passive"))
      (node (ref "T14") (pin "C") (pinfunction "C_C") (pintype "passive"))
    )
    (net (code "96") (name "Net-(LED17-PadA)") (class "Default")
      (node (ref "LED17") (pin "A") (pinfunction "A_A") (pintype "passive"))
      (node (ref "R62") (pin "2") (pinfunction "2_2") (pintype "passive"))
    )
    (net (code "97") (name "Net-(OLED1-RST)") (class "Default")
      (node (ref "JP5") (pin "16") (pinfunction "16_16") (pintype "passive"))
      (node (ref "OLED1") (pin "P$3") (pinfunction "RST_P$3") (pintype "bidirectional"))
    )
    (net (code "98") (name "Net-(OLED1-SCL)") (class "Default")
      (node (ref "JP5") (pin "7") (pinfunction "7_7") (pintype "passive"))
      (node (ref "OLED1") (pin "P$2") (pinfunction "SCL_P$2") (pintype "bidirectional"))
      (node (ref "R24") (pin "2") (pinfunction "2_2") (pintype "passive"))
    )
    (net (code "99") (name "Net-(OLED1-SDA)") (class "Default")
      (node (ref "JP5") (pin "10") (pinfunction "10_10") (pintype "passive"))
      (node (ref "OLED1") (pin "P$1") (pinfunction "SDA_P$1") (pintype "bidirectional"))
      (node (ref "R25") (pin "2") (pinfunction "2_2") (pintype "passive"))
    )
    (net (code "100") (name "Net-(R5-Pad1)") (class "Default")
      (node (ref "R5") (pin "1") (pinfunction "1_1") (pintype "passive"))
      (node (ref "U$1") (pin "8") (pinfunction "8_8") (pintype "bidirectional"))
    )
    (net (code "101") (name "Net-(R6-Pad1)") (class "Default")
      (node (ref "R6") (pin "1") (pinfunction "1_1") (pintype "passive"))
      (node (ref "U$1") (pin "9") (pinfunction "9_9") (pintype "bidirectional"))
    )
    (net (code "102") (name "Net-(R13-Pad1)") (class "Default")
      (node (ref "R13") (pin "1") (pinfunction "1_1") (pintype "passive"))
      (node (ref "U$1") (pin "C") (pinfunction "C_C") (pintype "bidirectional"))
    )
    (net (code "103") (name "Net-(R19-Pad1)") (class "Default")
      (node (ref "R19") (pin "1") (pinfunction "1_1") (pintype "passive"))
      (node (ref "U$1") (pin "10") (pinfunction "10_10") (pintype "bidirectional"))
    )
    (net (code "104") (name "Net-(R20-Pad1)") (class "Default")
      (node (ref "R20") (pin "1") (pinfunction "1_1") (pintype "passive"))
      (node (ref "U$1") (pin "11") (pinfunction "11_11") (pintype "bidirectional"))
    )
    (net (code "105") (name "Net-(R21-Pad1)") (class "Default")
      (node (ref "R21") (pin "1") (pinfunction "1_1") (pintype "passive"))
      (node (ref "U$1") (pin "12") (pinfunction "12_12") (pintype "bidirectional"))
    )
    (net (code "106") (name "Net-(R33-Pad1)") (class "Default")
      (node (ref "R33") (pin "1") (pinfunction "1_1") (pintype "passive"))
      (node (ref "U$1") (pin "2") (pinfunction "2_2") (pintype "bidirectional"))
    )
    (net (code "107") (name "Net-(R34-Pad1)") (class "Default")
      (node (ref "R34") (pin "1") (pinfunction "1_1") (pintype "passive"))
      (node (ref "U$1") (pin "3") (pinfunction "3_3") (pintype "bidirectional"))
    )
    (net (code "108") (name "Net-(R35-Pad1)") (class "Default")
      (node (ref "R35") (pin "1") (pinfunction "1_1") (pintype "passive"))
      (node (ref "U$1") (pin "4") (pinfunction "4_4") (pintype "bidirectional"))
    )
    (net (code "109") (name "Net-(R36-Pad1)") (class "Default")
      (node (ref "R36") (pin "1") (pinfunction "1_1") (pintype "passive"))
      (node (ref "U$1") (pin "5") (pinfunction "5_5") (pintype "bidirectional"))
    )
    (net (code "110") (name "Net-(R37-Pad1)") (class "Default")
      (node (ref "R37") (pin "1") (pinfunction "1_1") (pintype "passive"))
      (node (ref "U$1") (pin "6") (pinfunction "6_6") (pintype "bidirectional"))
    )
    (net (code "111") (name "Net-(R38-Pad1)") (class "Default")
      (node (ref "R38") (pin "1") (pinfunction "1_1") (pintype "passive"))
      (node (ref "U$1") (pin "7") (pinfunction "7_7") (pintype "bidirectional"))
    )
    (net (code "112") (name "Net-(S12A-P)") (class "Default")
      (node (ref "LED8") (pin "A") (pinfunction "A_A") (pintype "passive"))
      (node (ref "S12") (pin "2") (pinfunction "P_2") (pintype "passive"))
    )
    (net (code "113") (name "Net-(S12B-P)") (class "Default")
      (node (ref "R43") (pin "1") (pinfunction "1_1") (pintype "passive"))
      (node (ref "R44") (pin "1") (pinfunction "1_1") (pintype "passive"))
      (node (ref "S12") (pin "5") (pinfunction "P_5") (pintype "passive"))
    )
    (net (code "114") (name "Net-(S12B-S)") (class "Default")
      (node (ref "R42") (pin "2") (pinfunction "2_2") (pintype "passive"))
      (node (ref "S12") (pin "4") (pinfunction "S_4") (pintype "passive"))
    )
    (net (code "115") (name "Net-(U$7-P$4)") (class "Default")
      (node (ref "JP5") (pin "3") (pinfunction "3_3") (pintype "passive"))
      (node (ref "U$7") (pin "P2_1") (pinfunction "P$4_P2_1") (pintype "bidirectional"))
      (node (ref "U$7") (pin "P2_2") (pinfunction "P$5_P2_2") (pintype "bidirectional"))
      (node (ref "U$7") (pin "P2_3") (pinfunction "P$6_P2_3") (pintype "bidirectional"))
    )
    (net (code "116") (name "Net-(U$11-P$4)") (class "Default")
      (node (ref "JP5") (pin "5") (pinfunction "5_5") (pintype "passive"))
      (node (ref "U$11") (pin "P2_1") (pinfunction "P$4_P2_1") (pintype "bidirectional"))
      (node (ref "U$11") (pin "P2_2") (pinfunction "P$5_P2_2") (pintype "bidirectional"))
      (node (ref "U$11") (pin "P2_3") (pinfunction "P$6_P2_3") (pintype "bidirectional"))
    )
    (net (code "117") (name "Net-(U$14-1)") (class "Default")
      (node (ref "R47") (pin "1") (pinfunction "1_1") (pintype "passive"))
      (node (ref "R49") (pin "2") (pinfunction "2_2") (pintype "passive"))
      (node (ref "U$14") (pin "1-09") (pinfunction "1_1-09") (pintype "bidirectional"))
    )
    (net (code "118") (name "Net-(U$14-3)") (class "Default")
      (node (ref "R46") (pin "1") (pinfunction "1_1") (pintype "passive"))
      (node (ref "R48") (pin "2") (pinfunction "2_2") (pintype "passive"))
      (node (ref "U$14") (pin "3-09") (pinfunction "3_3-09") (pintype "bidirectional"))
    )
    (net (code "119") (name "Net-(U$33-P$4)") (class "Default")
      (node (ref "JP5") (pin "6") (pinfunction "6_6") (pintype "passive"))
      (node (ref "U$33") (pin "P2_1") (pinfunction "P$4_P2_1") (pintype "bidirectional"))
      (node (ref "U$33") (pin "P2_2") (pinfunction "P$5_P2_2") (pintype "bidirectional"))
      (node (ref "U$33") (pin "P2_3") (pinfunction "P$6_P2_3") (pintype "bidirectional"))
    )
    (net (code "120") (name "Net-(U$39-P$4)") (class "Default")
      (node (ref "JP5") (pin "4") (pinfunction "4_4") (pintype "passive"))
      (node (ref "U$39") (pin "P2_1") (pinfunction "P$4_P2_1") (pintype "bidirectional"))
      (node (ref "U$39") (pin "P2_2") (pinfunction "P$5_P2_2") (pintype "bidirectional"))
      (node (ref "U$39") (pin "P2_3") (pinfunction "P$6_P2_3") (pintype "bidirectional"))
    )
    (net (code "121") (name "Net-(U$40-P$4)") (class "Default")
      (node (ref "JP5") (pin "8") (pinfunction "8_8") (pintype "passive"))
      (node (ref "U$40") (pin "P2_1") (pinfunction "P$4_P2_1") (pintype "bidirectional"))
      (node (ref "U$40") (pin "P2_2") (pinfunction "P$5_P2_2") (pintype "bidirectional"))
      (node (ref "U$40") (pin "P2_3") (pinfunction "P$6_P2_3") (pintype "bidirectional"))
    )
    (net (code "122") (name "Net-(U$42-P$4)") (class "Default")
      (node (ref "JP6") (pin "13") (pinfunction "13_13") (pintype "passive"))
      (node (ref "U$42") (pin "P2_1") (pinfunction "P$4_P2_1") (pintype "bidirectional"))
      (node (ref "U$42") (pin "P2_2") (pinfunction "P$5_P2_2") (pintype "bidirectional"))
      (node (ref "U$42") (pin "P2_3") (pinfunction "P$6_P2_3") (pintype "bidirectional"))
    )
    (net (code "123") (name "Net-(U$43-P$4)") (class "Default")
      (node (ref "JP6") (pin "15") (pinfunction "15_15") (pintype "passive"))
      (node (ref "U$43") (pin "P2_1") (pinfunction "P$4_P2_1") (pintype "bidirectional"))
      (node (ref "U$43") (pin "P2_2") (pinfunction "P$5_P2_2") (pintype "bidirectional"))
      (node (ref "U$43") (pin "P2_3") (pinfunction "P$6_P2_3") (pintype "bidirectional"))
    )
    (net (code "124") (name "Net-(U$44-P$4)") (class "Default")
      (node (ref "JP6") (pin "20") (pinfunction "20_20") (pintype "passive"))
      (node (ref "U$44") (pin "P2_1") (pinfunction "P$4_P2_1") (pintype "bidirectional"))
      (node (ref "U$44") (pin "P2_2") (pinfunction "P$5_P2_2") (pintype "bidirectional"))
      (node (ref "U$44") (pin "P2_3") (pinfunction "P$6_P2_3") (pintype "bidirectional"))
    )
    (net (code "125") (name "Net-(U$45-P$4)") (class "Default")
      (node (ref "JP6") (pin "19") (pinfunction "19_19") (pintype "passive"))
      (node (ref "U$45") (pin "P2_1") (pinfunction "P$4_P2_1") (pintype "bidirectional"))
      (node (ref "U$45") (pin "P2_2") (pinfunction "P$5_P2_2") (pintype "bidirectional"))
      (node (ref "U$45") (pin "P2_3") (pinfunction "P$6_P2_3") (pintype "bidirectional"))
    )
    (net (code "126") (name "Net-(U$48-P$4)") (class "Default")
      (node (ref "JP6") (pin "18") (pinfunction "18_18") (pintype "passive"))
      (node (ref "U$48") (pin "P2_1") (pinfunction "P$4_P2_1") (pintype "bidirectional"))
      (node (ref "U$48") (pin "P2_2") (pinfunction "P$5_P2_2") (pintype "bidirectional"))
      (node (ref "U$48") (pin "P2_3") (pinfunction "P$6_P2_3") (pintype "bidirectional"))
    )
    (net (code "127") (name "unconnected-(IC11-CTRL-PadP$3)") (class "Default")
      (node (ref "IC11") (pin "P$3") (pinfunction "CTRL_P$3") (pintype "bidirectional"))
    )
    (net (code "128") (name "unconnected-(IC12-CTL-PadP$3)") (class "Default")
      (node (ref "IC12") (pin "P$3") (pinfunction "CTL_P$3") (pintype "bidirectional"))
    )
    (net (code "129") (name "unconnected-(IC13-NOCON-Pad5)") (class "Default")
      (node (ref "IC13") (pin "5") (pinfunction "NOCON_5") (pintype "bidirectional"))
    )
    (net (code "130") (name "unconnected-(J1-PadR)") (class "Default")
      (node (ref "J1") (pin "R") (pinfunction "R_R") (pintype "bidirectional"))
    )
    (net (code "131") (name "unconnected-(J1-PadRN)") (class "Default")
      (node (ref "J1") (pin "RN") (pinfunction "RN_RN") (pintype "bidirectional"))
    )
    (net (code "132") (name "unconnected-(J1-PadSN)") (class "Default")
      (node (ref "J1") (pin "SN") (pinfunction "SN_SN") (pintype "bidirectional"))
    )
    (net (code "133") (name "unconnected-(J1-PadTN)") (class "Default")
      (node (ref "J1") (pin "TN") (pinfunction "TN_TN") (pintype "bidirectional"))
    )
    (net (code "134") (name "unconnected-(J3-PadRN)") (class "Default")
      (node (ref "J3") (pin "RN") (pinfunction "RN_RN") (pintype "bidirectional"))
    )
    (net (code "135") (name "unconnected-(J3-PadSN)") (class "Default")
      (node (ref "J3") (pin "SN") (pinfunction "SN_SN") (pintype "bidirectional"))
    )
    (net (code "136") (name "unconnected-(J3-PadTN)") (class "Default")
      (node (ref "J3") (pin "TN") (pinfunction "TN_TN") (pintype "bidirectional"))
    )
    (net (code "137") (name "unconnected-(J4-PadRN)") (class "Default")
      (node (ref "J4") (pin "RN") (pinfunction "RN_RN") (pintype "bidirectional"))
    )
    (net (code "138") (name "unconnected-(J4-PadSN)") (class "Default")
      (node (ref "J4") (pin "SN") (pinfunction "SN_SN") (pintype "bidirectional"))
    )
    (net (code "139") (name "unconnected-(J4-PadTN)") (class "Default")
      (node (ref "J4") (pin "TN") (pinfunction "TN_TN") (pintype "bidirectional"))
    )
    (net (code "140") (name "unconnected-(J9-PadRN)") (class "Default")
      (node (ref "J9") (pin "RN") (pinfunction "RN_RN") (pintype "bidirectional"))
    )
    (net (code "141") (name "unconnected-(J9-PadSN)") (class "Default")
      (node (ref "J9") (pin "SN") (pinfunction "SN_SN") (pintype "bidirectional"))
    )
    (net (code "142") (name "unconnected-(J9-PadTN)") (class "Default")
      (node (ref "J9") (pin "TN") (pinfunction "TN_TN") (pintype "bidirectional"))
    )
    (net (code "143") (name "unconnected-(J10-SWITCH-Pad3)") (class "Default")
      (node (ref "J10") (pin "3") (pinfunction "SWITCH_3") (pintype "bidirectional"))
    )
    (net (code "144") (name "unconnected-(JP5-Pad1)") (class "Default")
      (node (ref "JP5") (pin "1") (pinfunction "1_1") (pintype "passive"))
    )
    (net (code "145") (name "unconnected-(JP5-Pad2)") (class "Default")
      (node (ref "JP5") (pin "2") (pinfunction "2_2") (pintype "passive"))
    )
    (net (code "146") (name "unconnected-(X1-PadR)") (class "Default")
      (node (ref "X1") (pin "R") (pinfunction "R_R") (pintype "passive"))
    )
    (net (code "147") (name "unconnected-(X1-PadRS)") (class "Default")
      (node (ref "X1") (pin "RS") (pinfunction "RS_RS") (pintype "passive"))
    )
    (net (code "148") (name "unconnected-(X1-PadTS)") (class "Default")
      (node (ref "X1") (pin "TS") (pinfunction "TS_TS") (pintype "passive"))
    )
  )
)
